# 1379_control.net
KiCad netlist of a schematic drawn in EAGLE
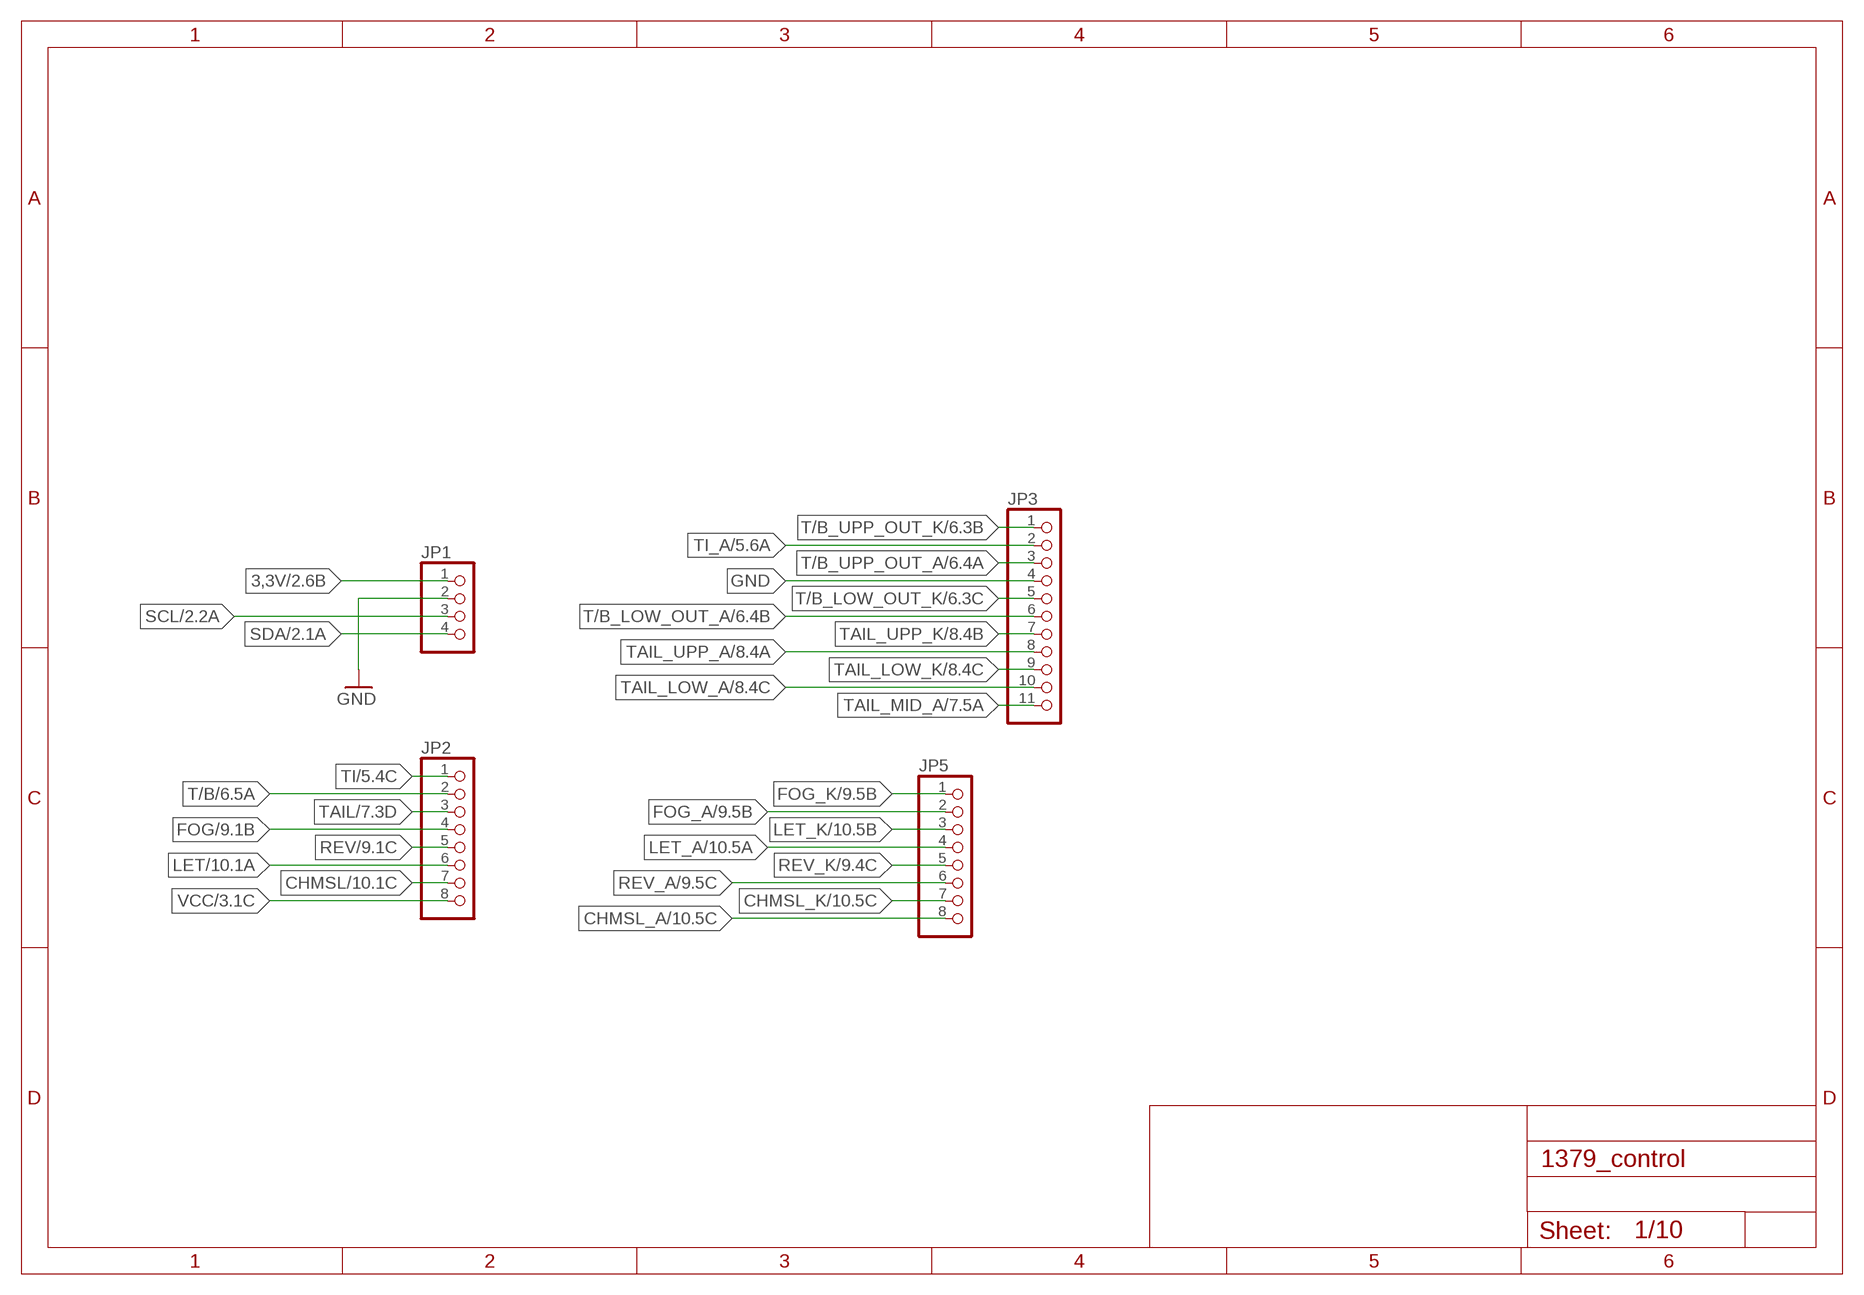
[diagram p0: schematic, sheet 1]
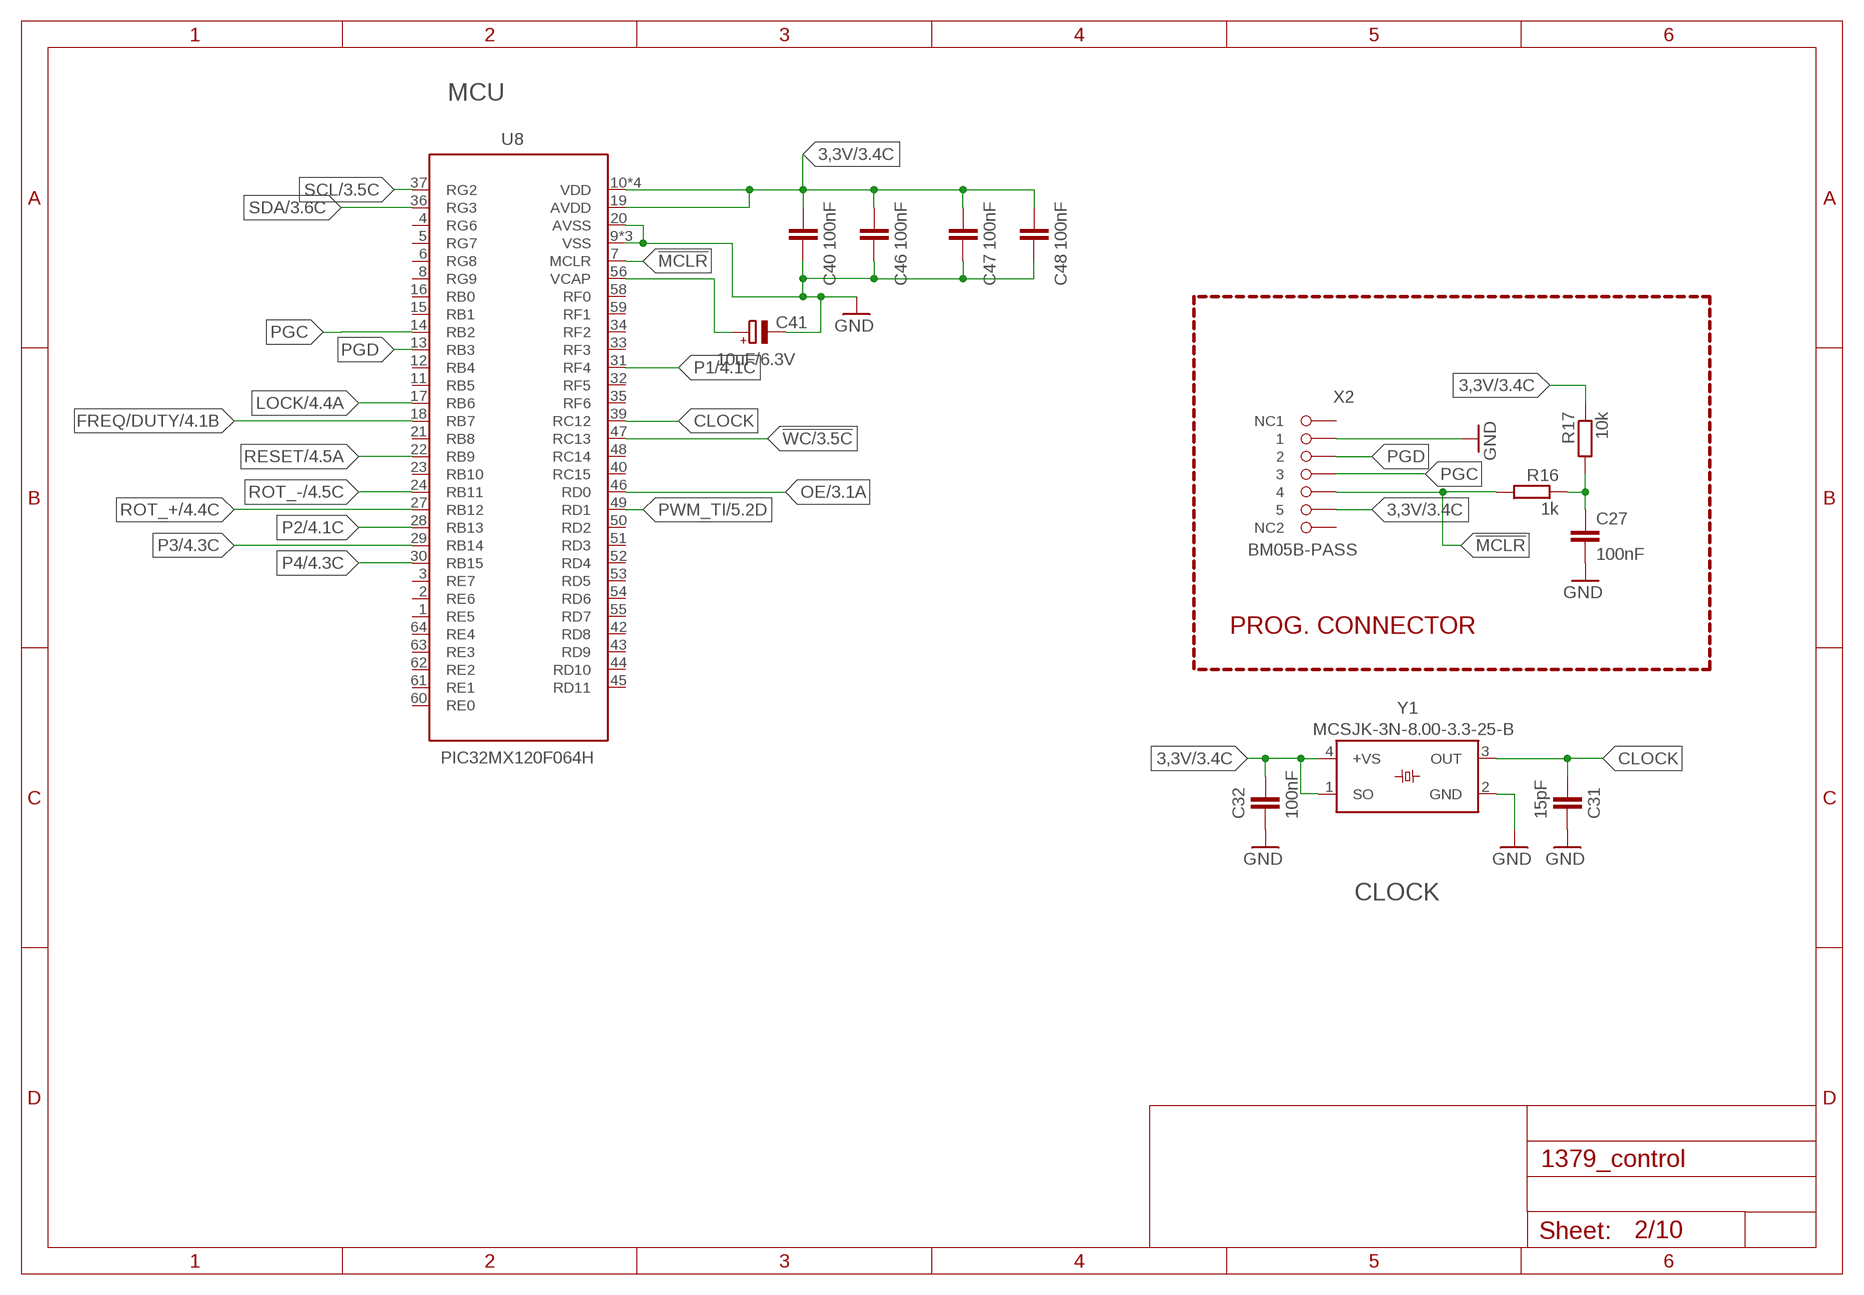
[diagram p1: schematic, sheet 2]
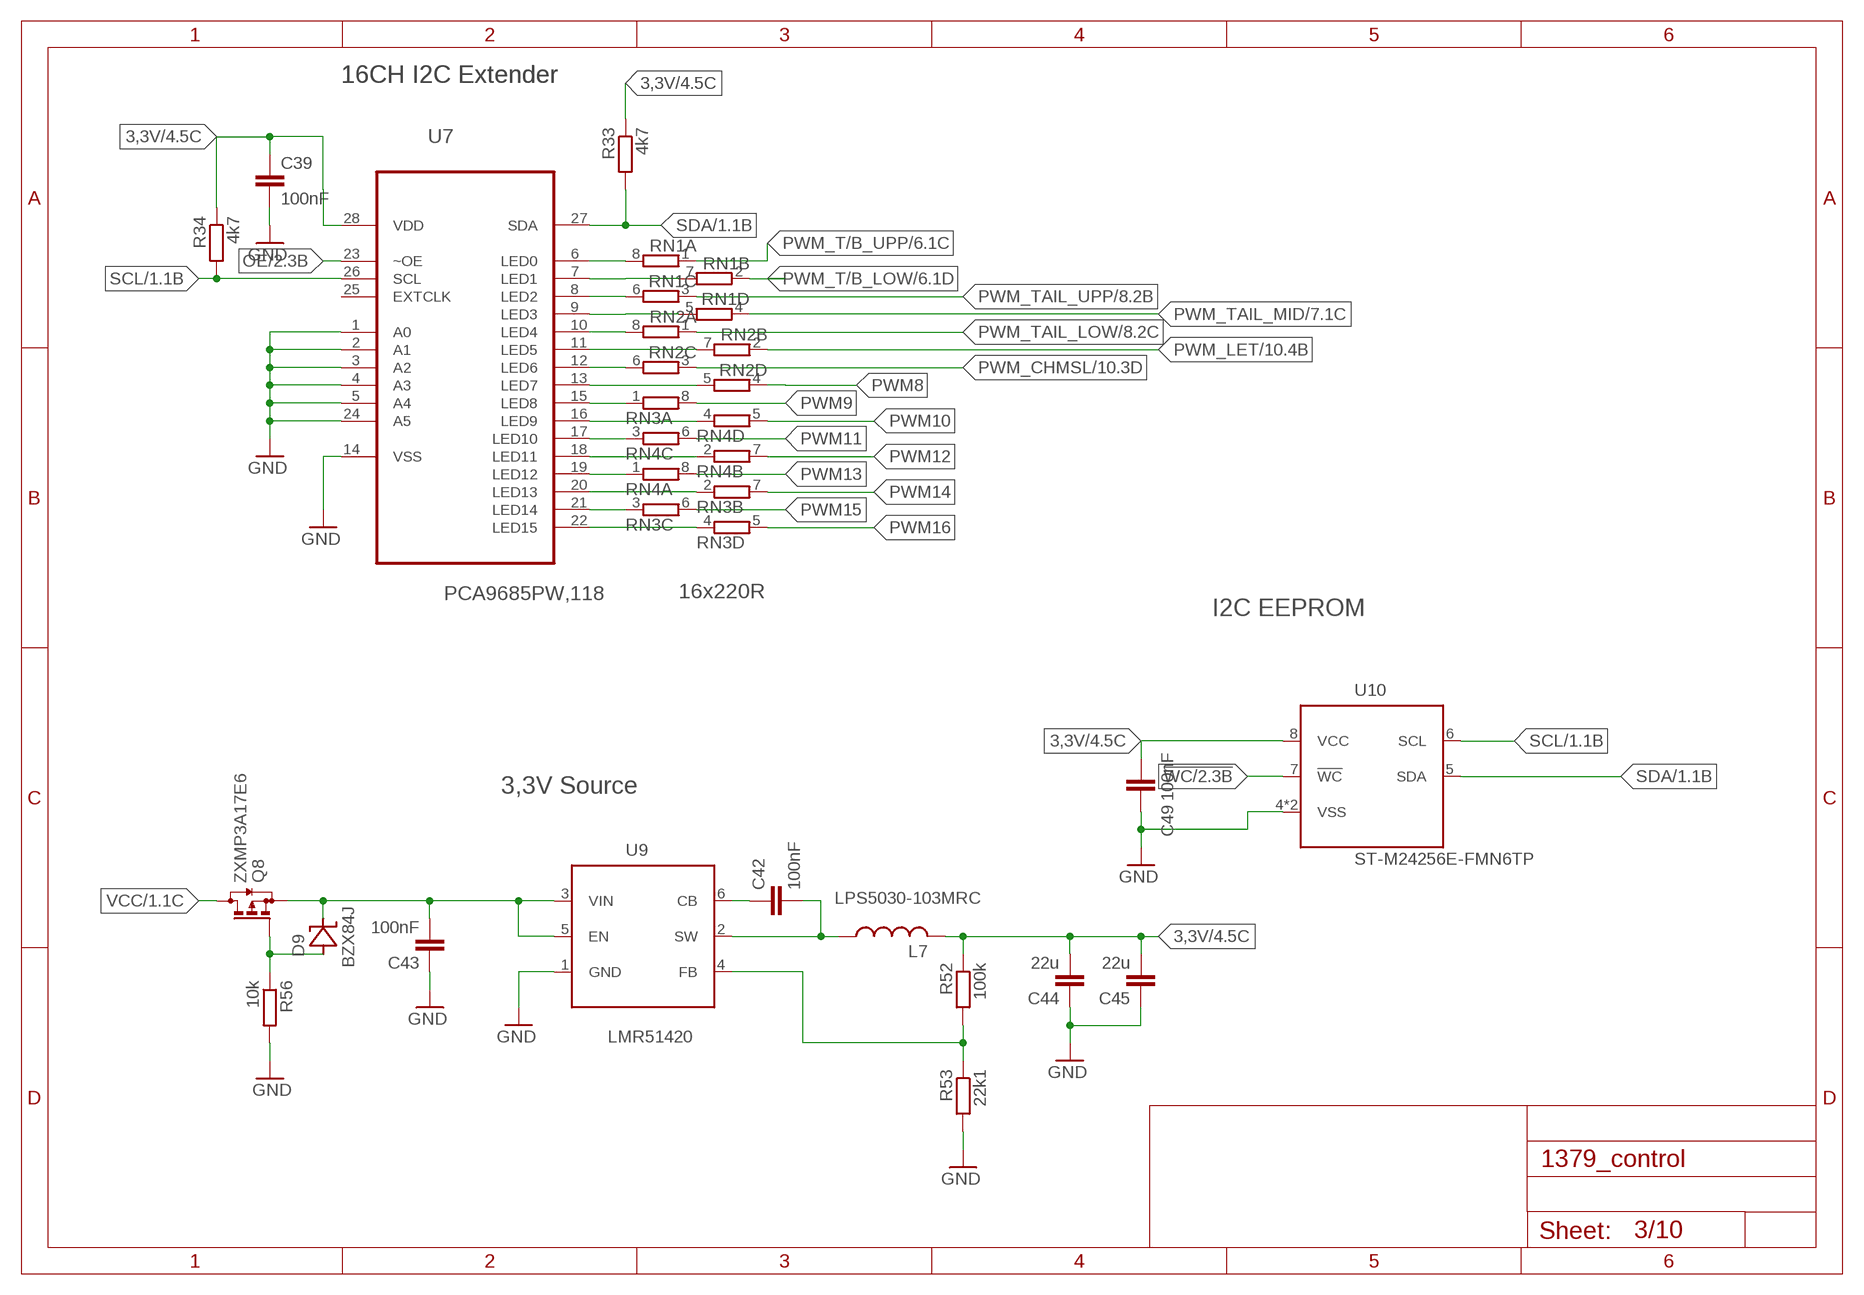
[diagram p2: schematic, sheet 3]
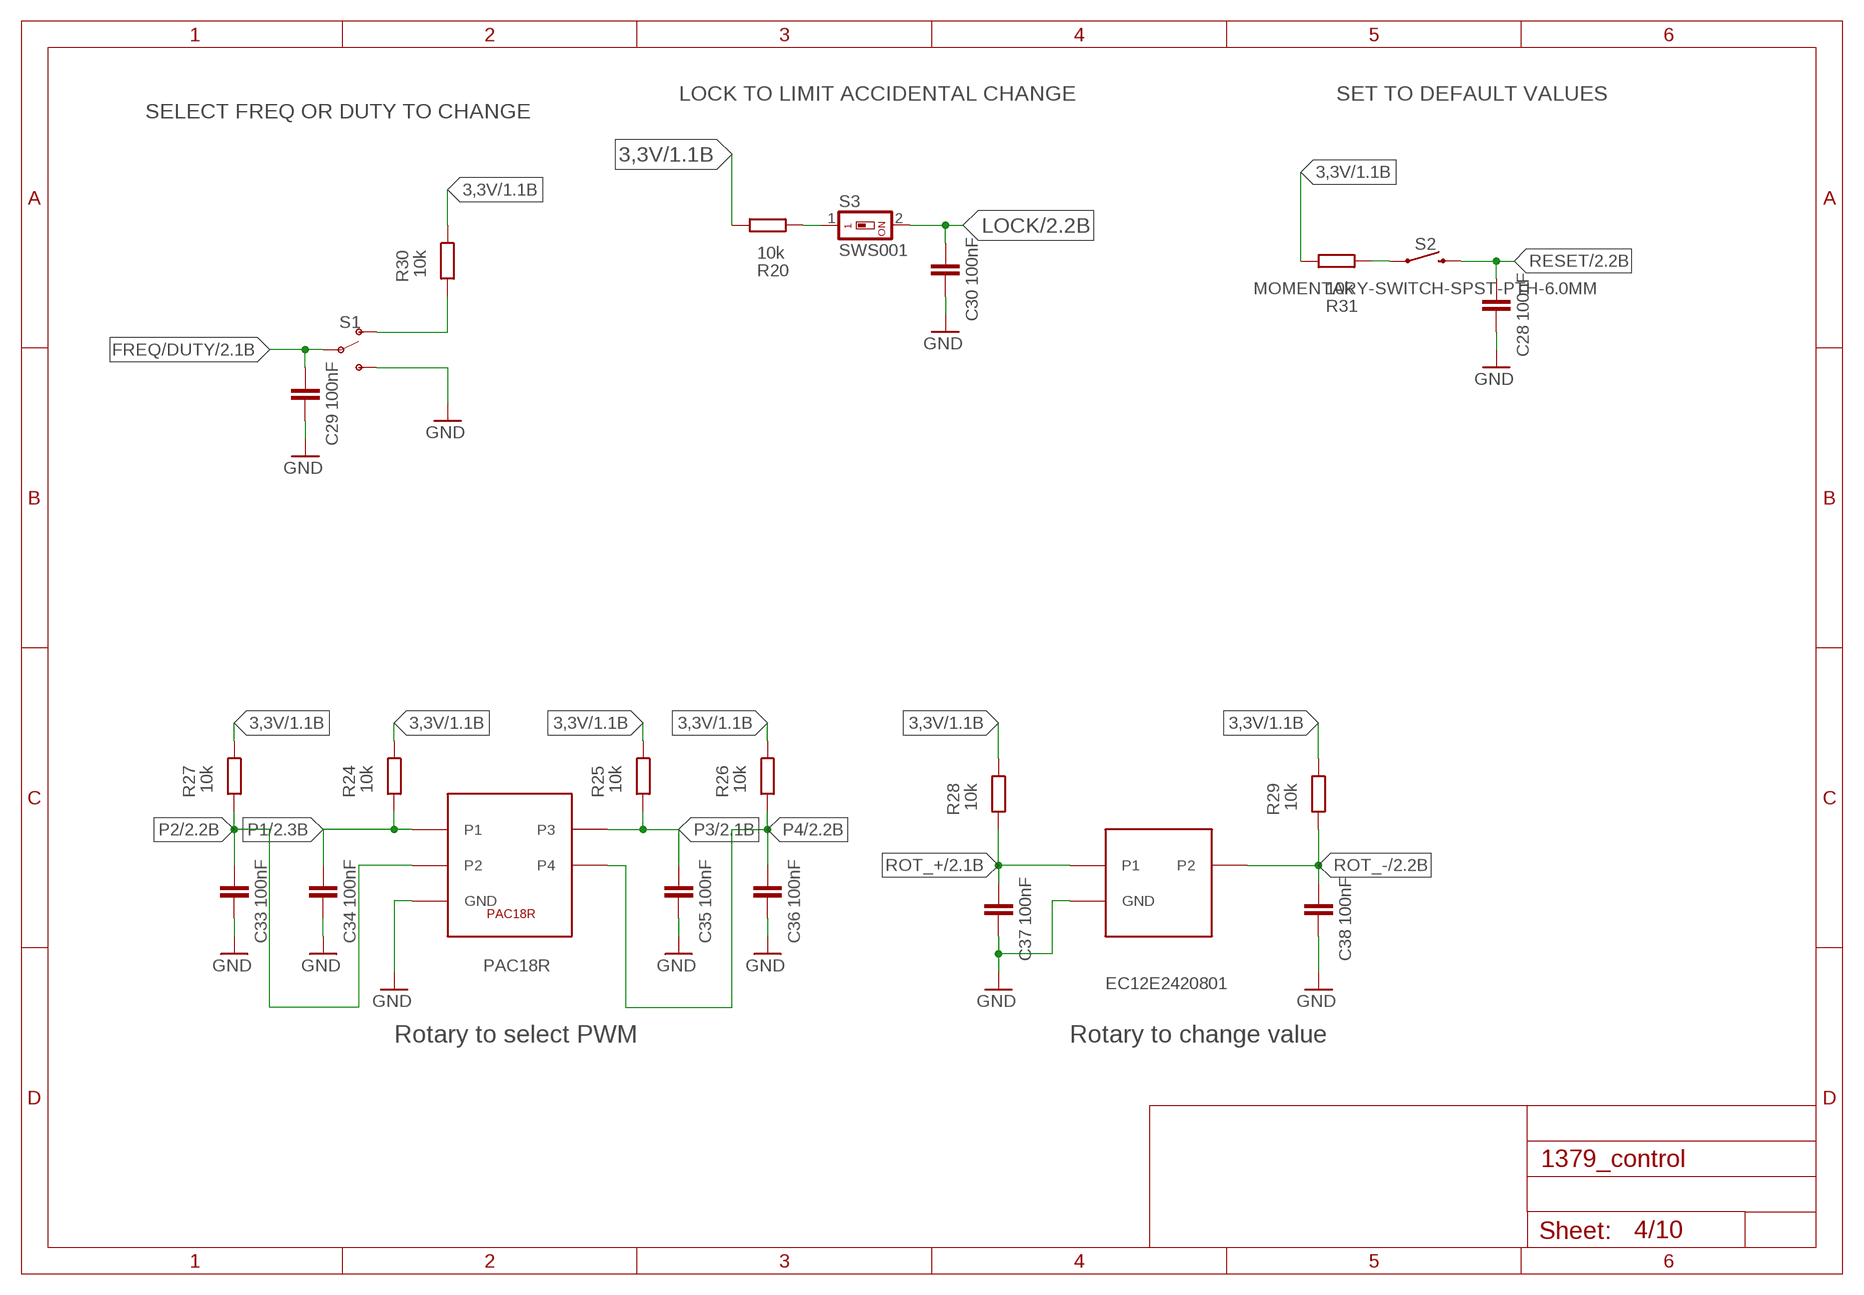
[diagram p3: schematic, sheet 4]
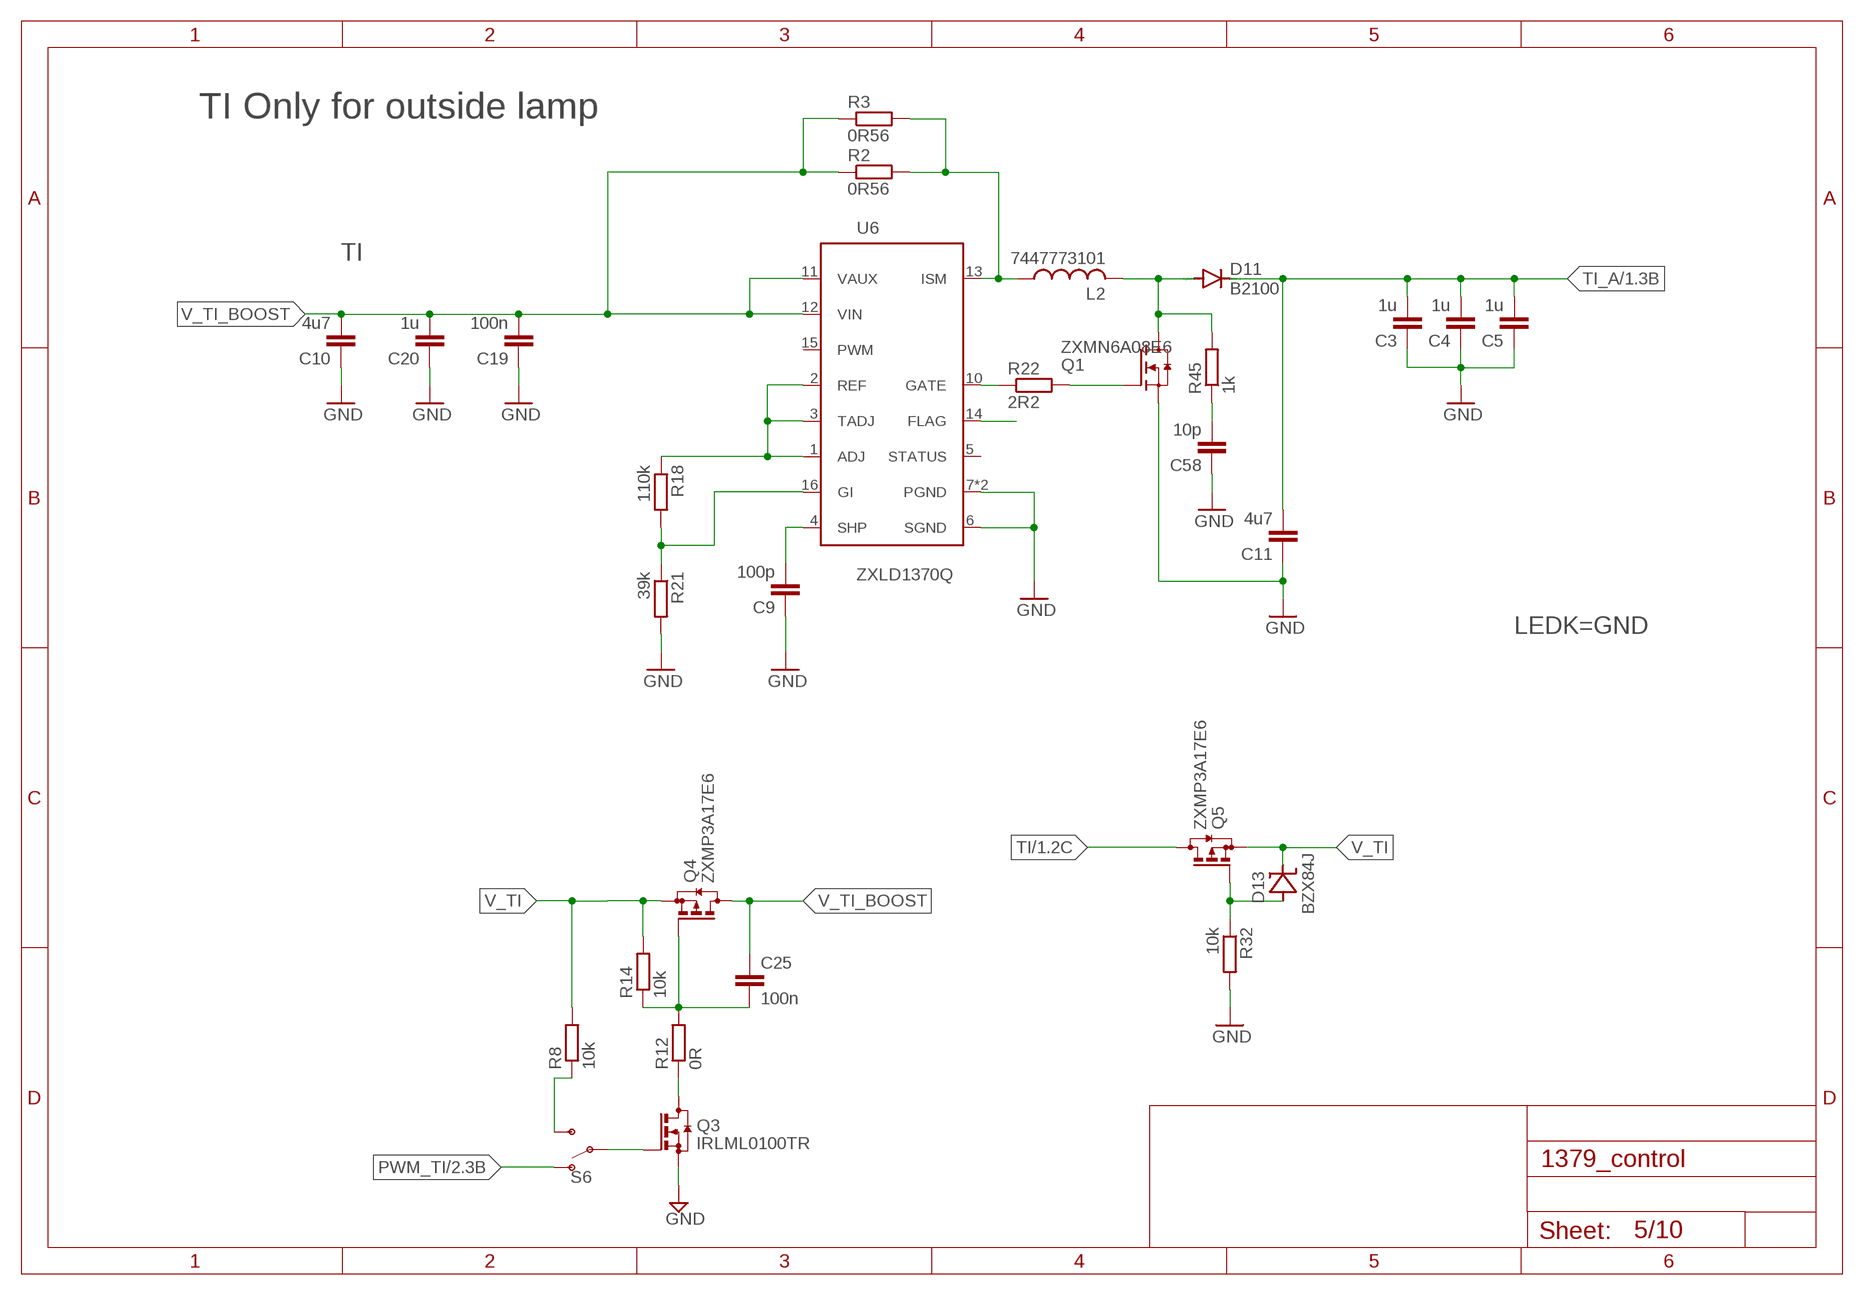
[diagram p4: schematic, sheet 5]
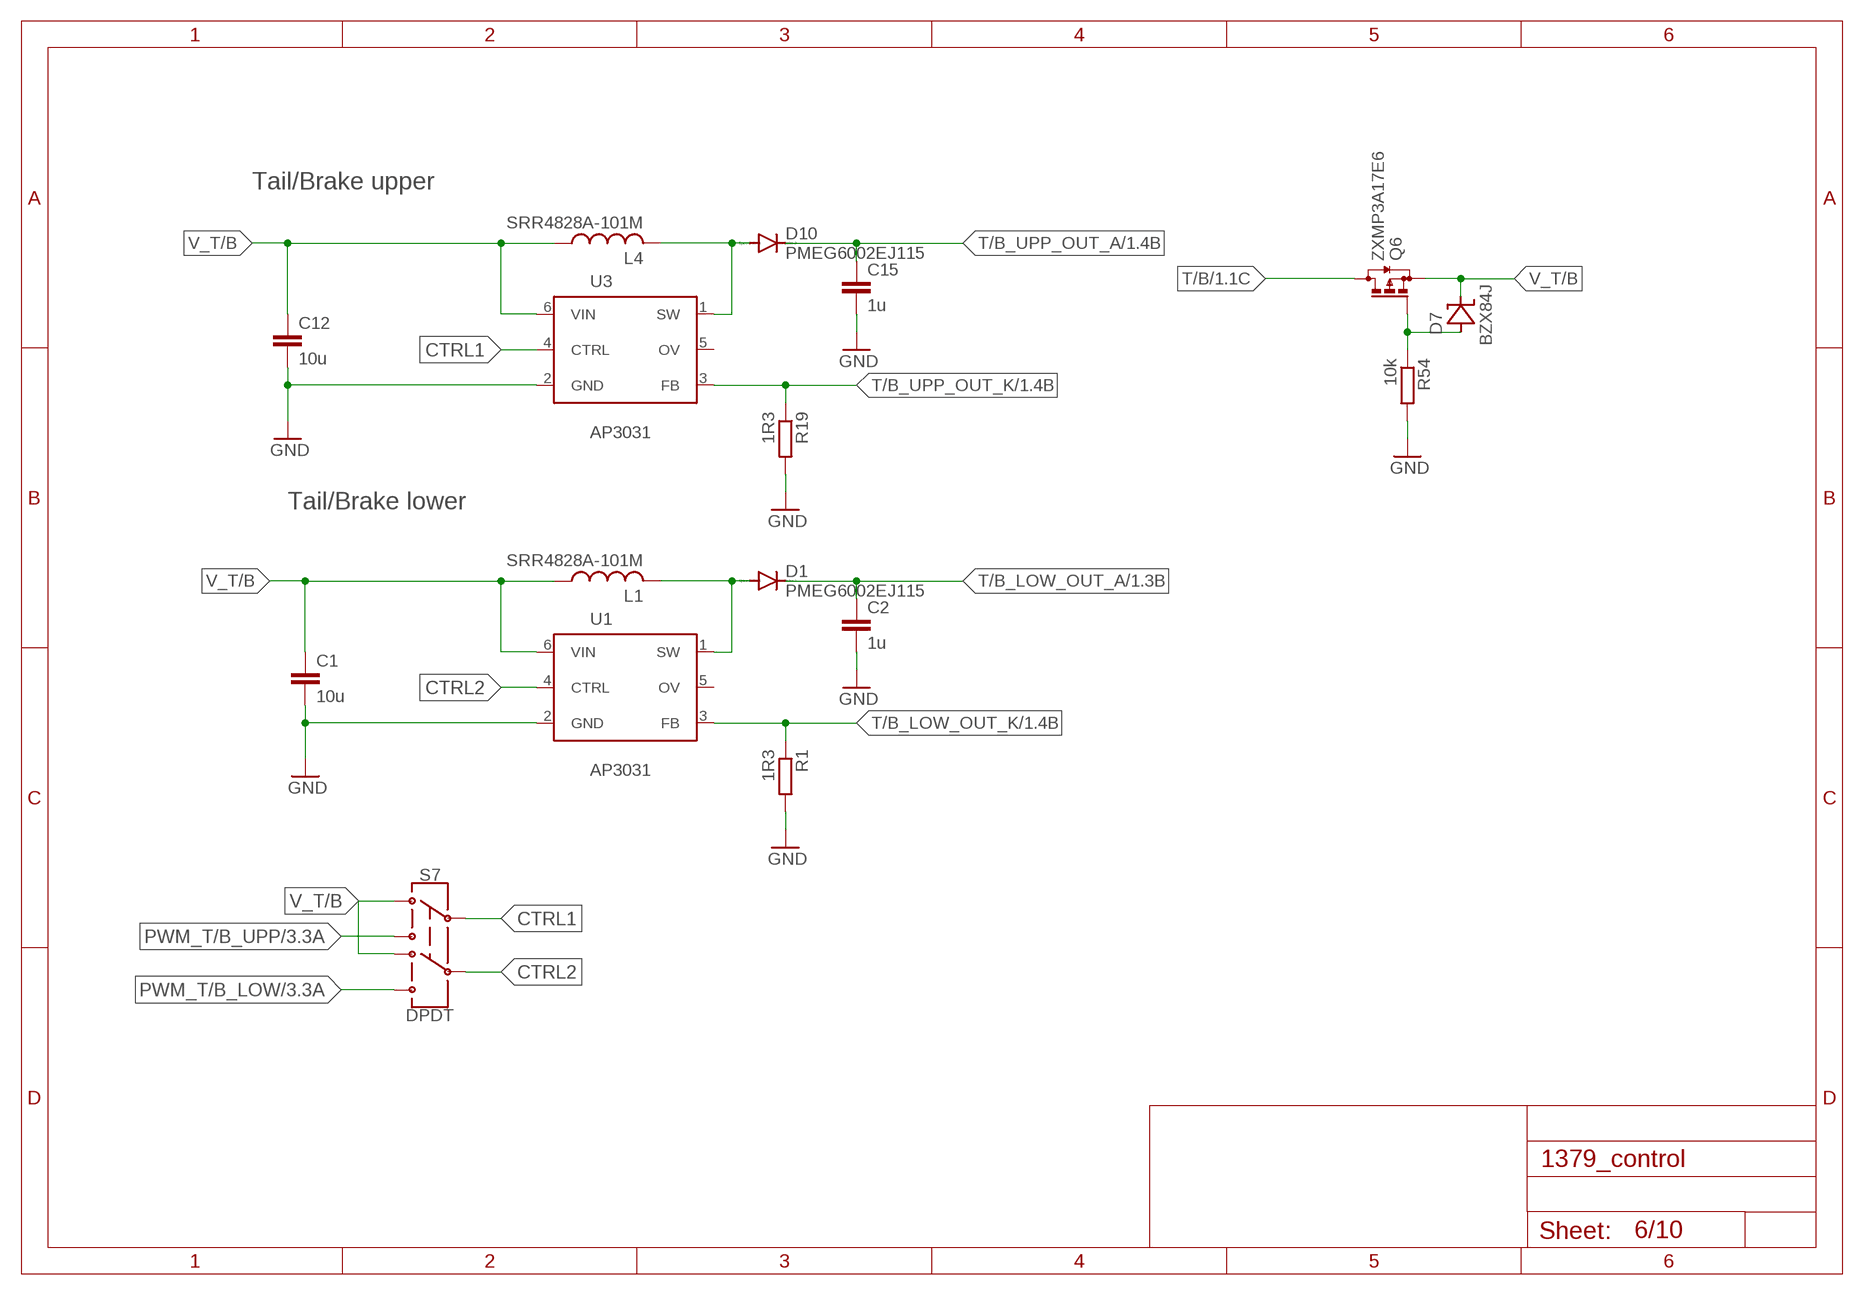
[diagram p5: schematic, sheet 6]
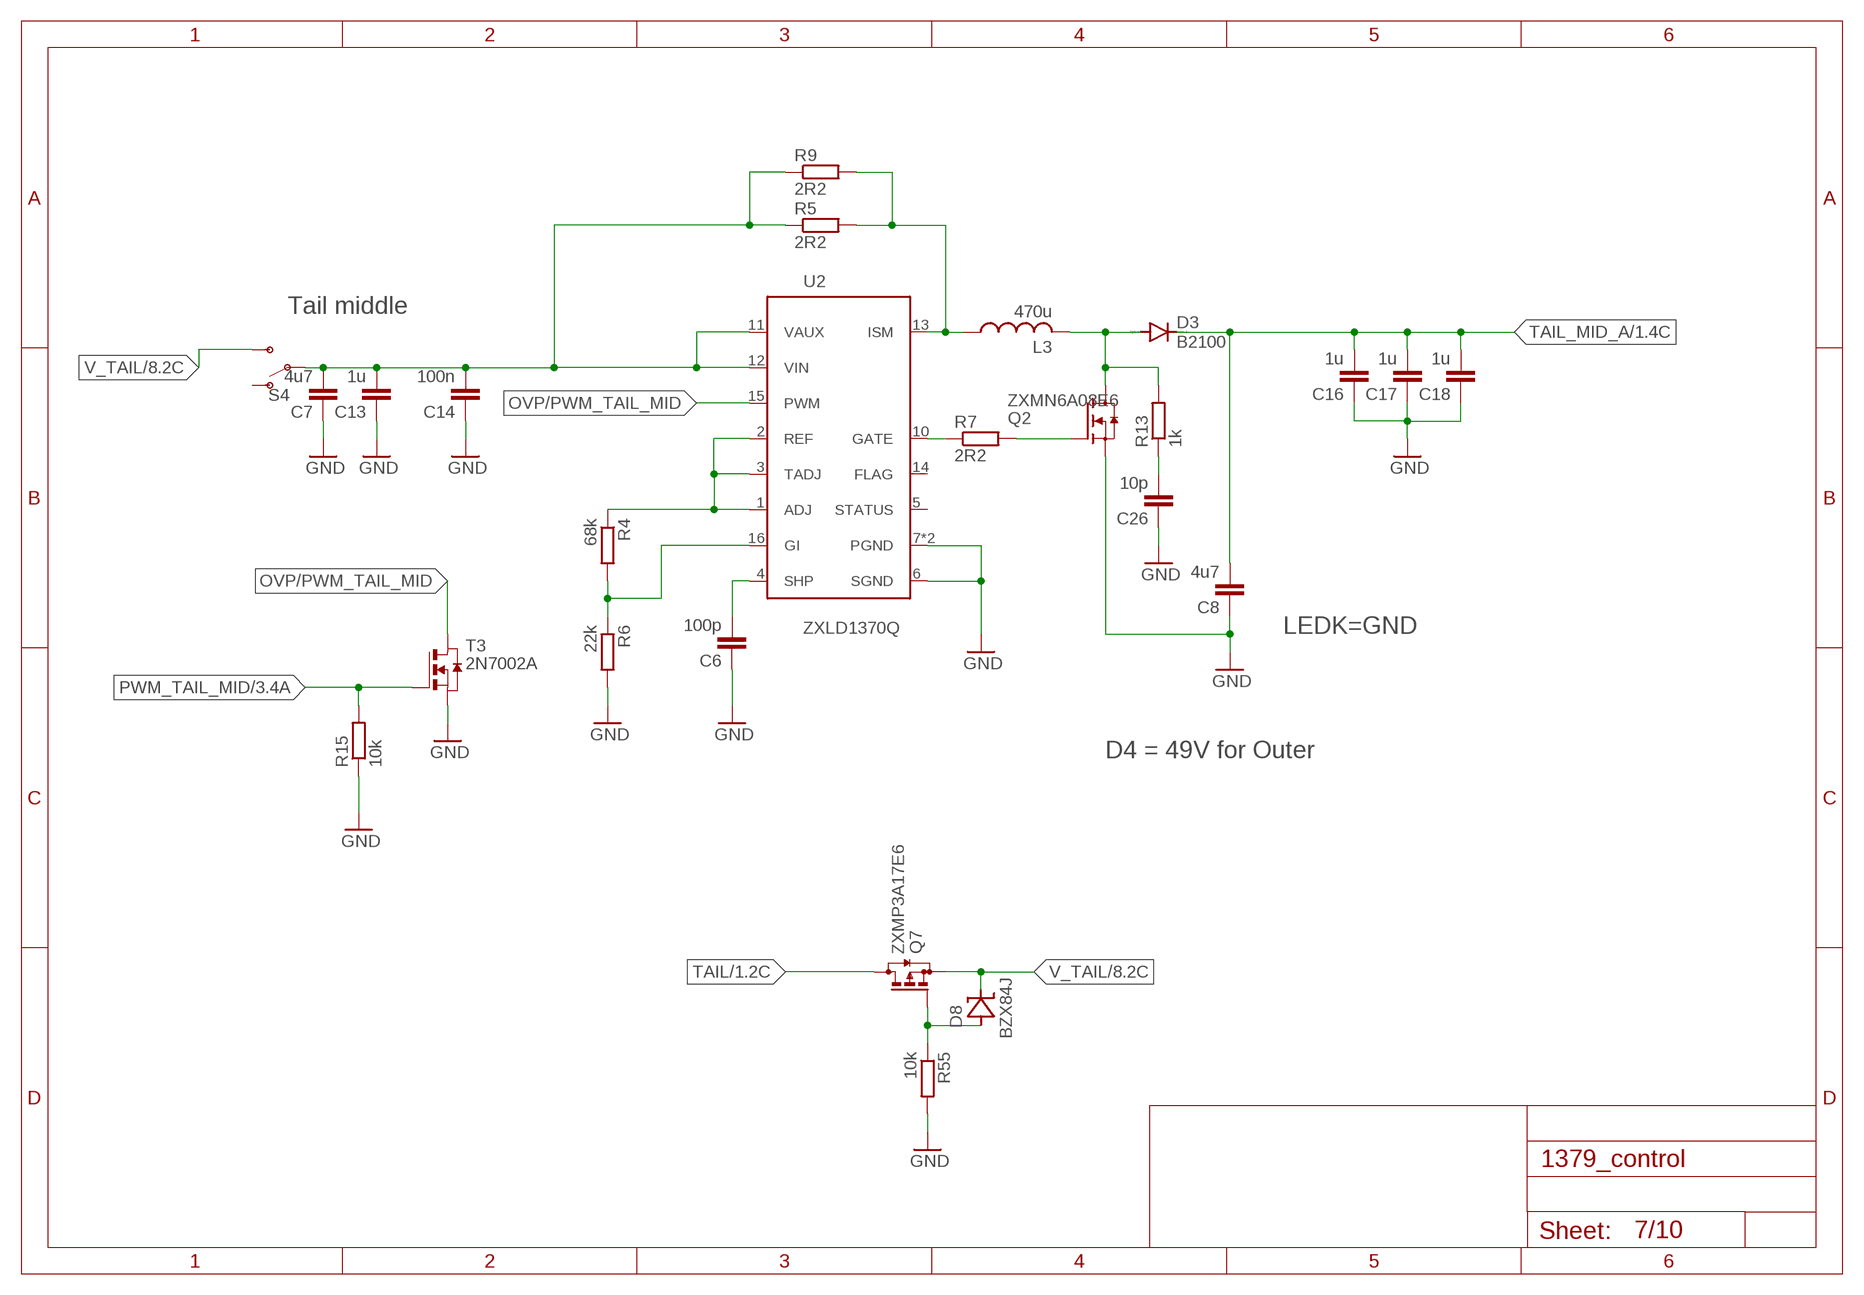
[diagram p6: schematic, sheet 7]
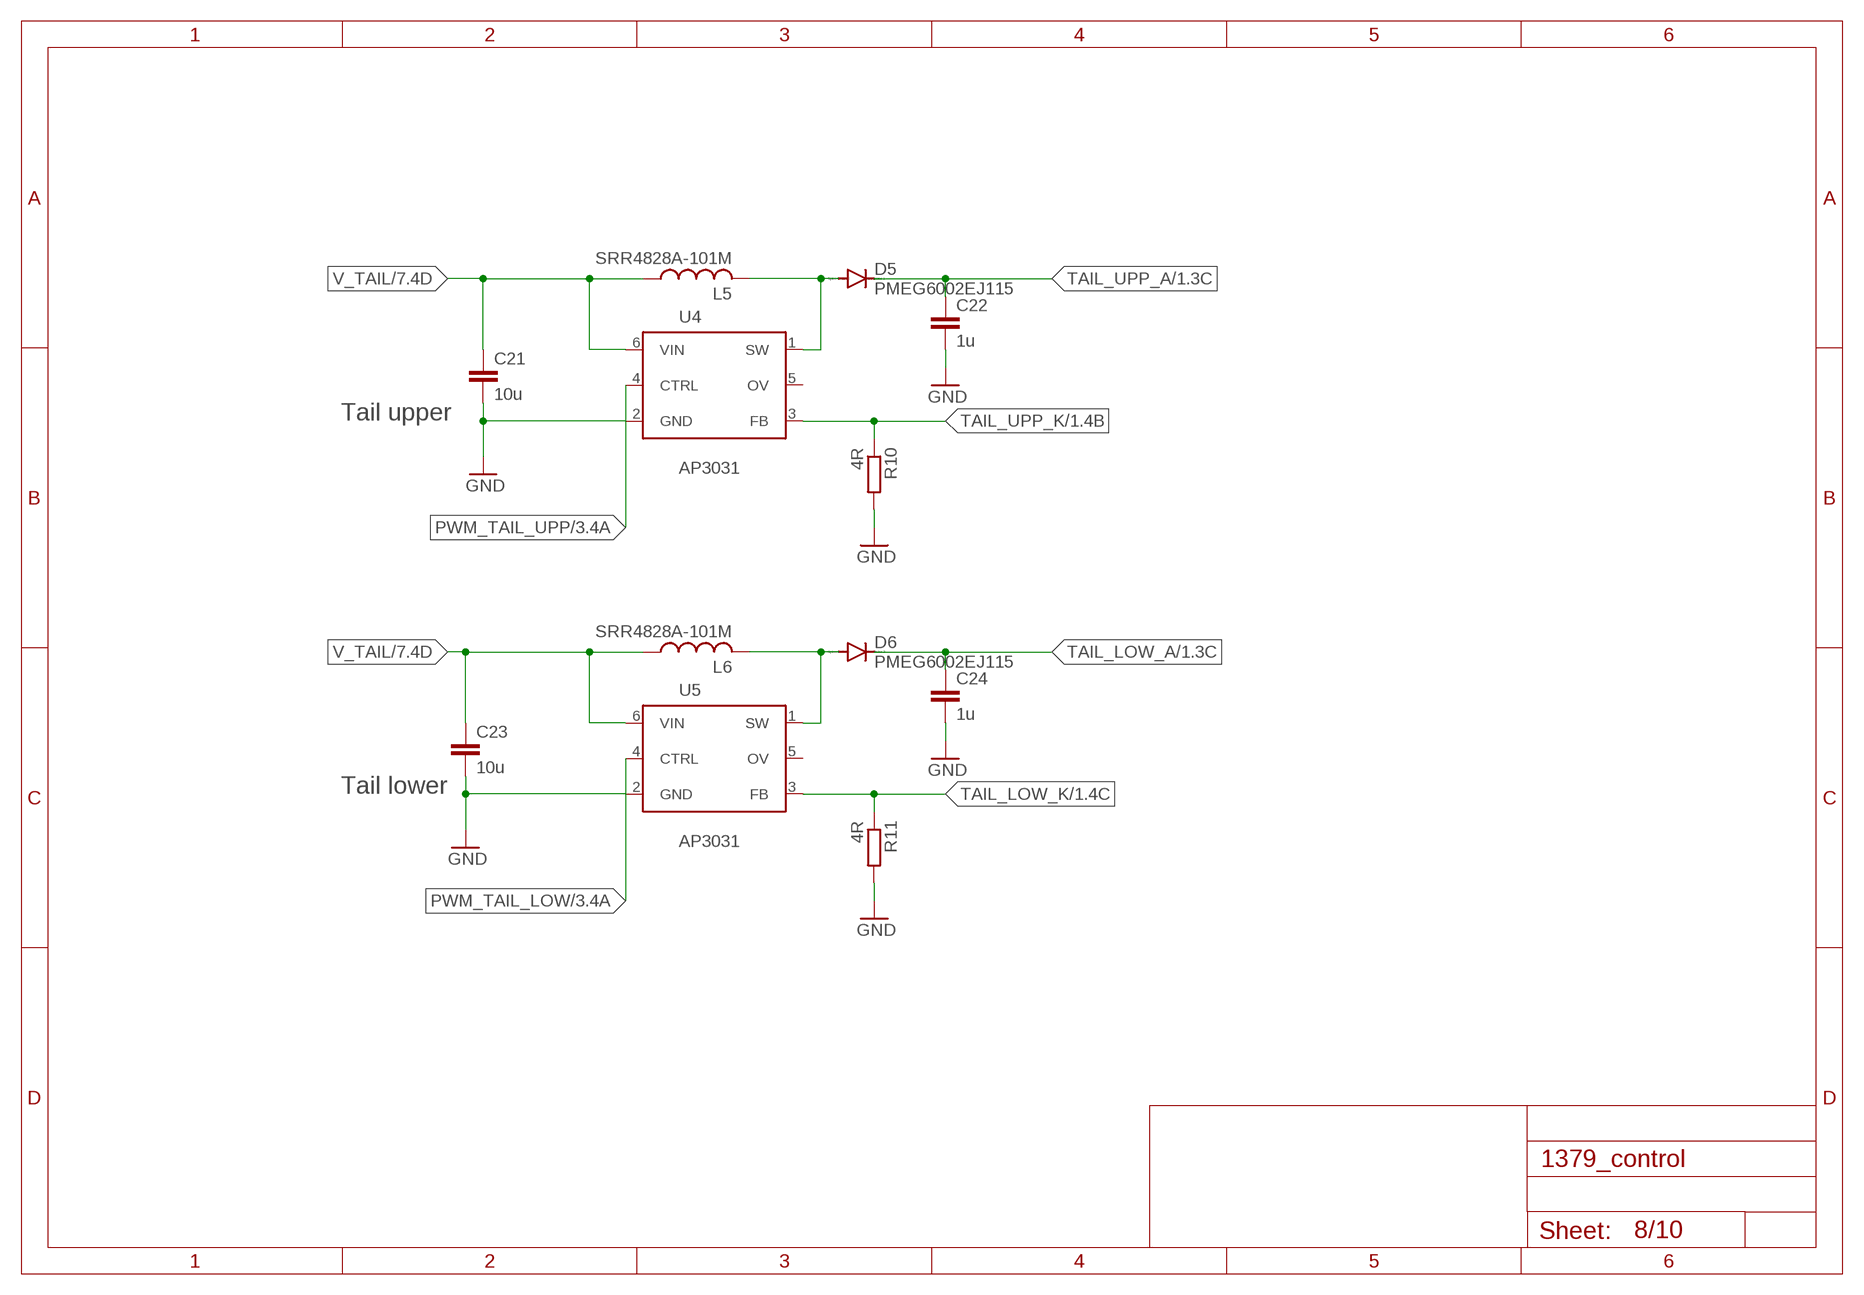
[diagram p7: schematic, sheet 8]
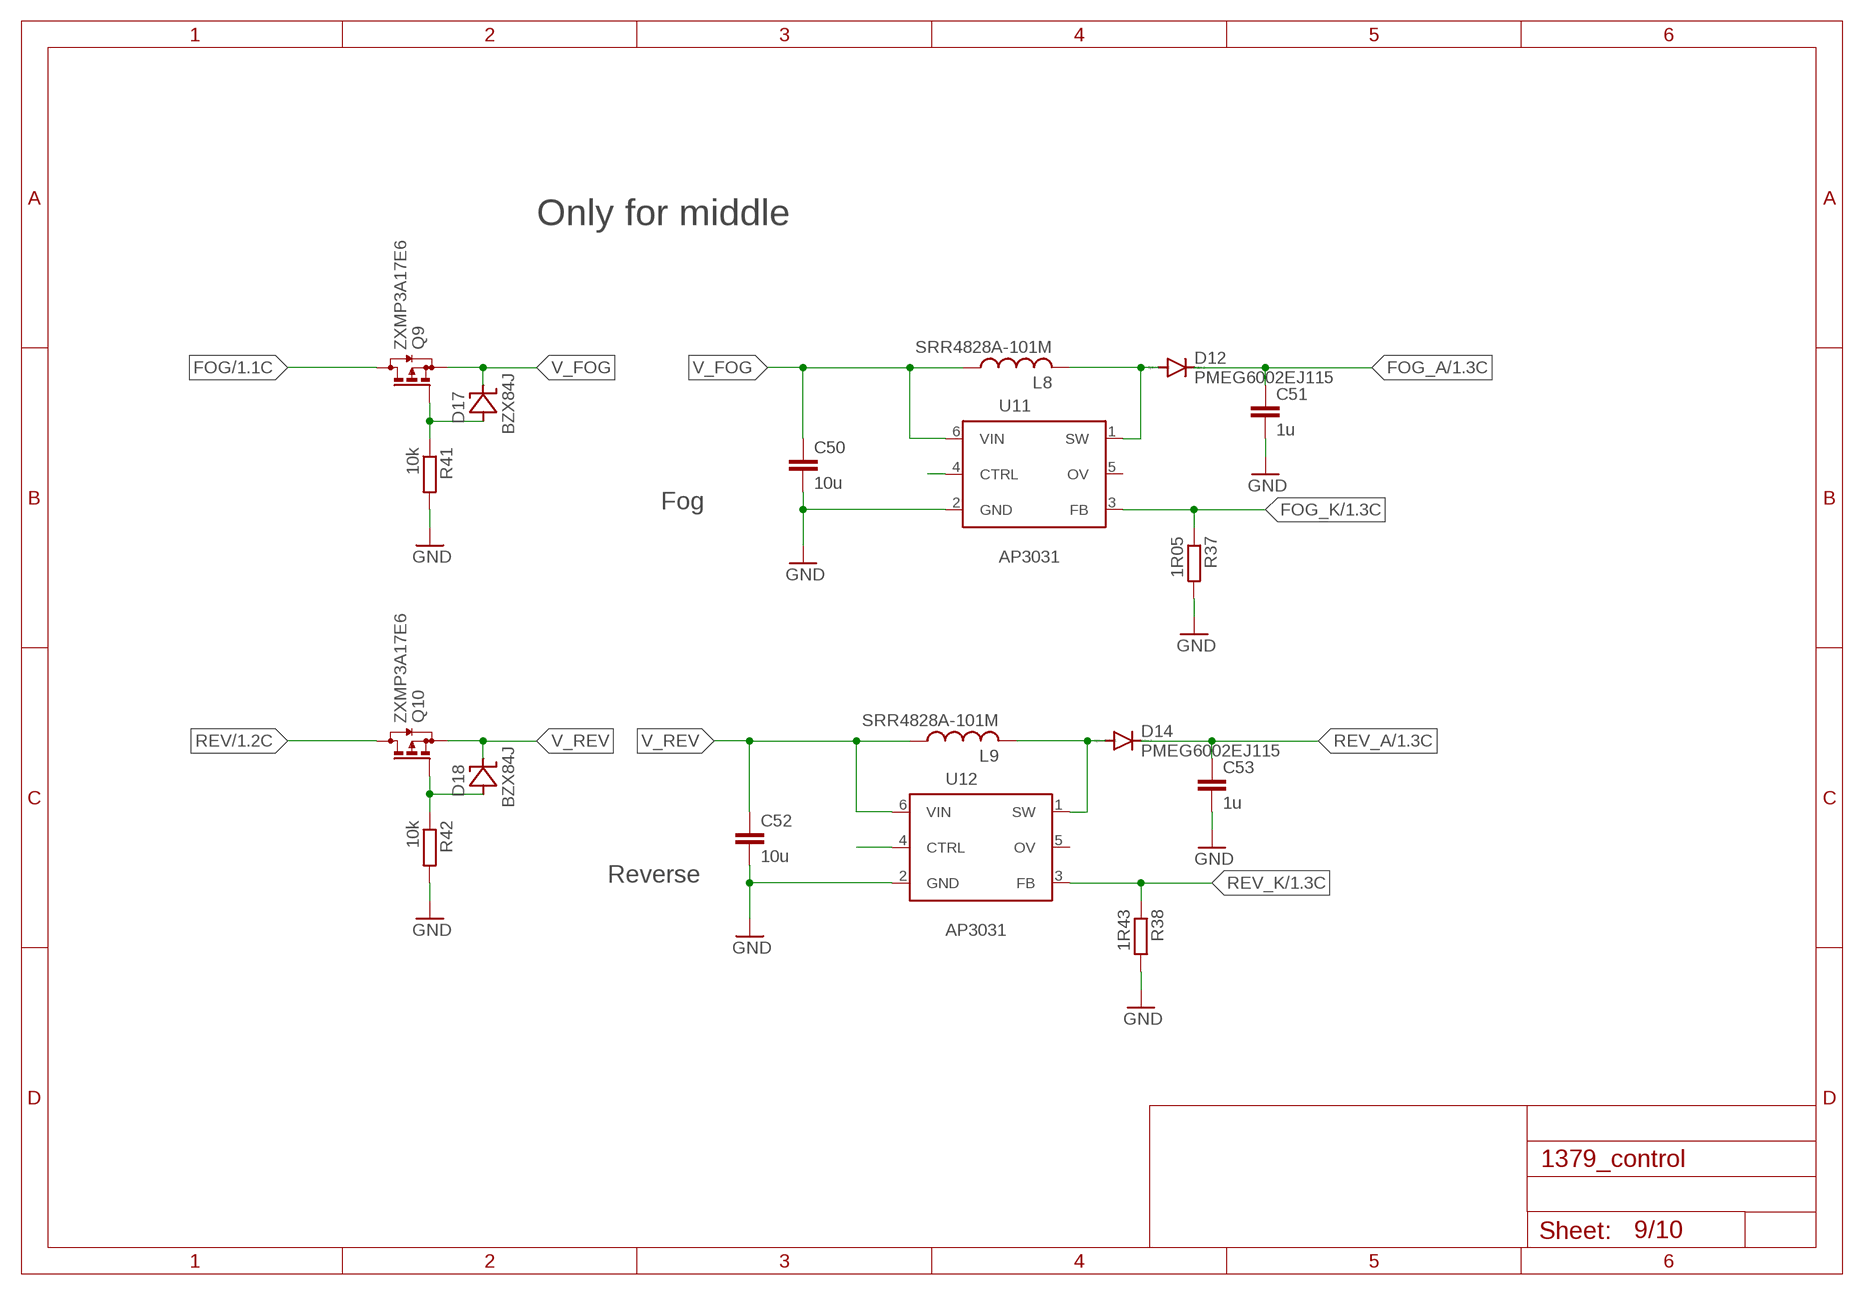
[diagram p8: schematic, sheet 9]
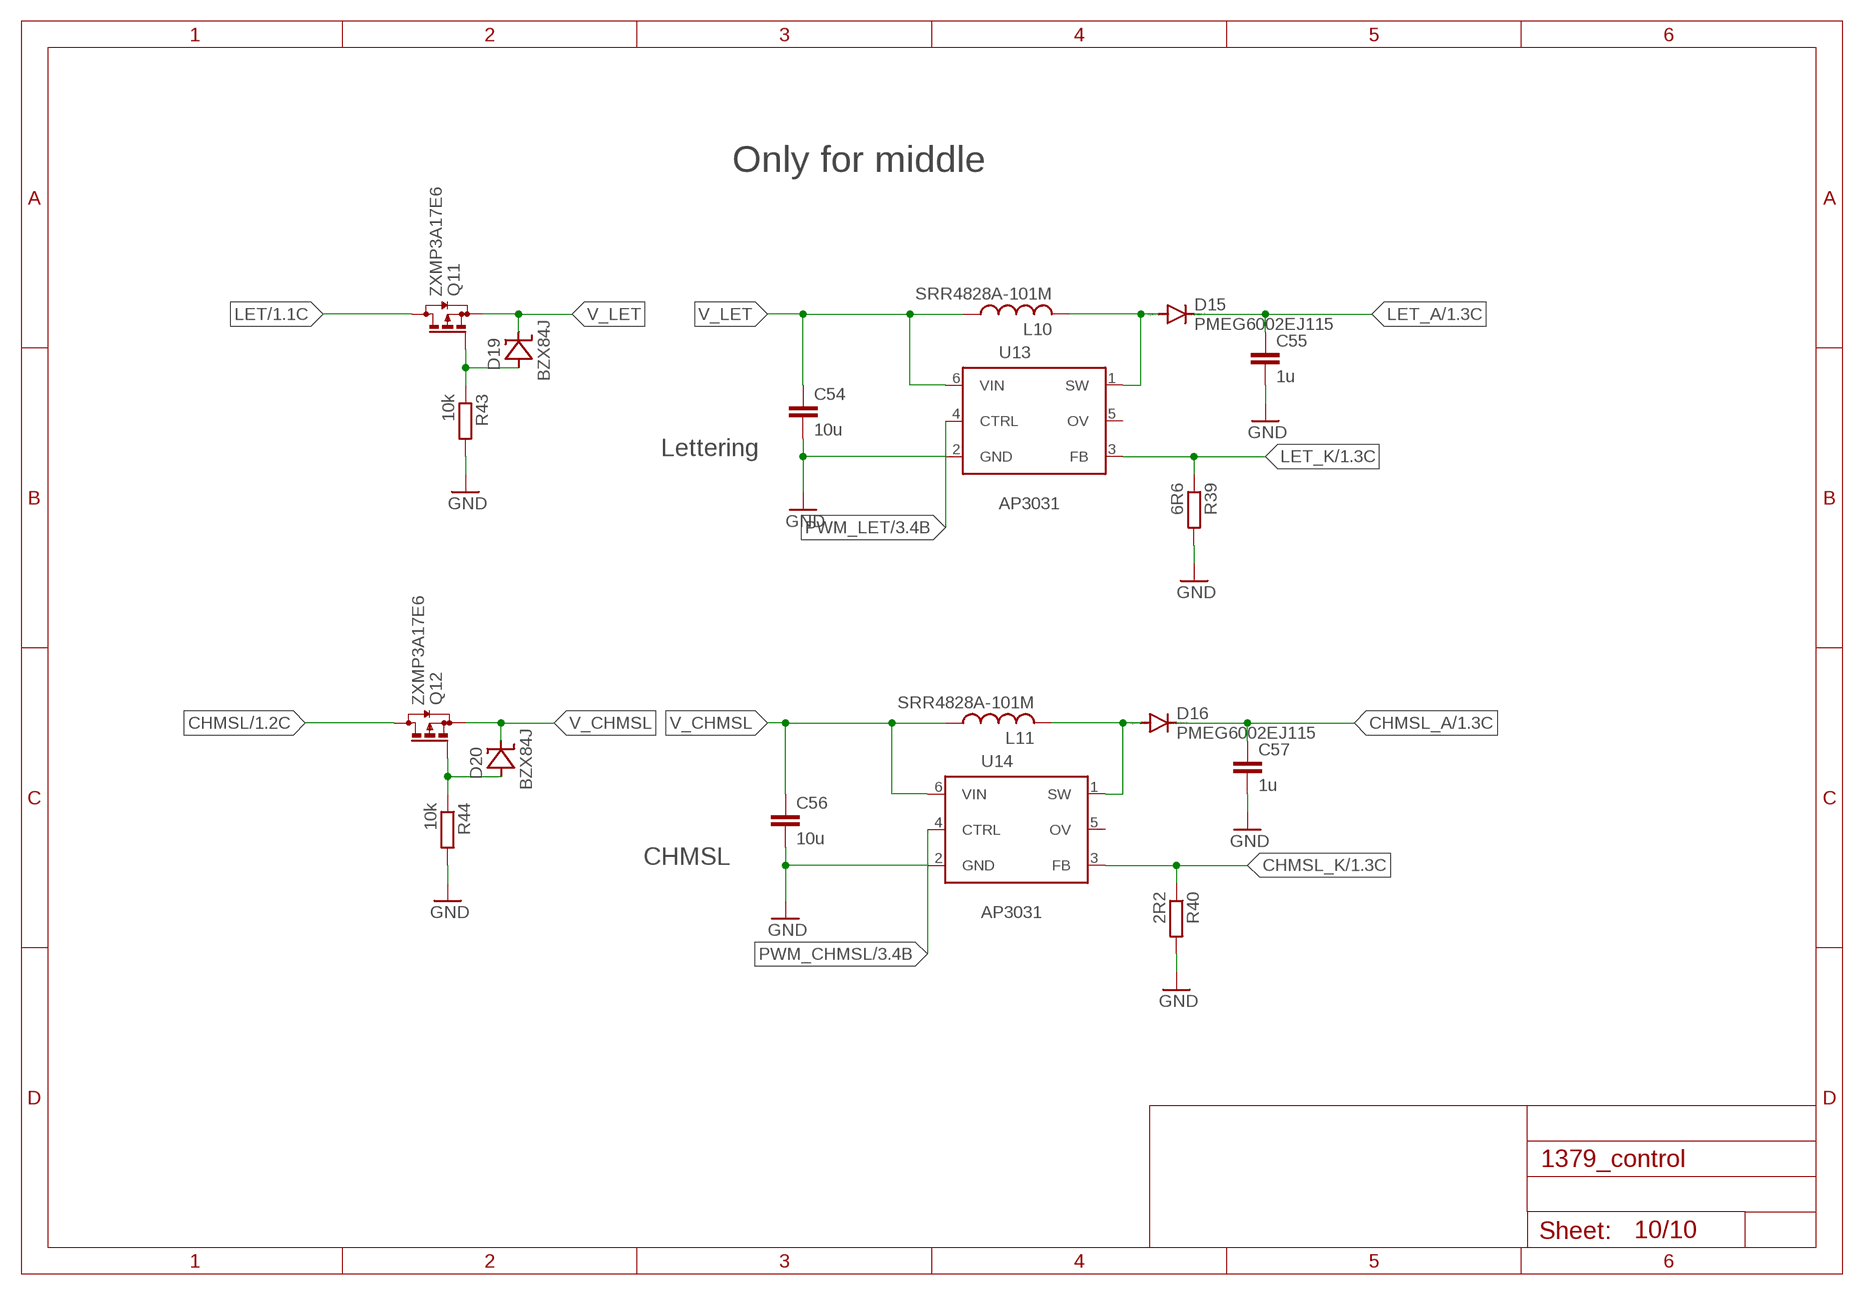
[diagram p9: schematic, sheet 10]

(export (version "E")
  (design (tool "Eeschema 10.0.6"))
  (components
    (comp (ref "C1")
      (value "10u")
      (footprint "eagle-import:C0805")
      (libsource (lib "eagle-import") (part "rcl_334_C-EUC0805"))
    )
    (comp (ref "C2")
      (value "1u")
      (footprint "eagle-import:C0805")
      (libsource (lib "eagle-import") (part "rcl_334_C-EUC0805"))
    )
    (comp (ref "C12")
      (value "10u")
      (footprint "eagle-import:C0805")
      (libsource (lib "eagle-import") (part "rcl_334_C-EUC0805"))
    )
    (comp (ref "C15")
      (value "1u")
      (footprint "eagle-import:C0805")
      (libsource (lib "eagle-import") (part "rcl_334_C-EUC0805"))
    )
    (comp (ref "D1")
      (value "PMEG6002EJ115")
      (footprint "eagle-import:SOD323-R")
      (libsource (lib "eagle-import") (part "DIODE-SOD323-R"))
    )
    (comp (ref "D7")
      (value "BZX84J")
      (footprint "eagle-import:SOD323")
      (libsource (lib "eagle-import") (part "BZX84J"))
    )
    (comp (ref "D10")
      (value "PMEG6002EJ115")
      (footprint "eagle-import:SOD323-R")
      (libsource (lib "eagle-import") (part "DIODE-SOD323-R"))
    )
    (comp (ref "L1")
      (value "SRR4828A-101M")
      (footprint "eagle-import:L_5X5")
      (libsource (lib "eagle-import") (part "POWER_INDUCTOR5X5"))
    )
    (comp (ref "L4")
      (value "SRR4828A-101M")
      (footprint "eagle-import:L_5X5")
      (libsource (lib "eagle-import") (part "POWER_INDUCTOR5X5"))
    )
    (comp (ref "Q6")
      (value "ZXMP3A17E6")
      (footprint "eagle-import:SOT23-6")
      (libsource (lib "eagle-import") (part "ZXMP3A17E6"))
    )
    (comp (ref "R1")
      (value "1R3")
      (footprint "eagle-import:R0805")
      (libsource (lib "eagle-import") (part "rcl_334_R-EU_R0805"))
    )
    (comp (ref "R19")
      (value "1R3")
      (footprint "eagle-import:R0805")
      (libsource (lib "eagle-import") (part "rcl_334_R-EU_R0805"))
    )
    (comp (ref "R54")
      (value "10k")
      (footprint "eagle-import:R0603")
      (libsource (lib "eagle-import") (part "rcl_334_R-EU_R0603"))
    )
    (comp (ref "S7")
      (value "DPDT")
      (footprint "eagle-import:SWITCH_DPDT_PTH_GPI-152-3013")
      (libsource (lib "eagle-import") (part "DPDT"))
    )
    (comp (ref "U1")
      (value "AP3031")
      (footprint "eagle-import:SOT23-6")
      (libsource (lib "eagle-import") (part "AP3031"))
    )
    (comp (ref "U3")
      (value "AP3031")
      (footprint "eagle-import:SOT23-6")
      (libsource (lib "eagle-import") (part "AP3031"))
    )
    (comp (ref "C54")
      (value "10u")
      (footprint "eagle-import:C0805")
      (libsource (lib "eagle-import") (part "rcl_334_C-EUC0805"))
    )
    (comp (ref "C55")
      (value "1u")
      (footprint "eagle-import:C0805")
      (libsource (lib "eagle-import") (part "rcl_334_C-EUC0805"))
    )
    (comp (ref "C56")
      (value "10u")
      (footprint "eagle-import:C0805")
      (libsource (lib "eagle-import") (part "rcl_334_C-EUC0805"))
    )
    (comp (ref "C57")
      (value "1u")
      (footprint "eagle-import:C0805")
      (libsource (lib "eagle-import") (part "rcl_334_C-EUC0805"))
    )
    (comp (ref "D15")
      (value "PMEG6002EJ115")
      (footprint "eagle-import:SOD323-R")
      (libsource (lib "eagle-import") (part "DIODE-SOD323-R"))
    )
    (comp (ref "D16")
      (value "PMEG6002EJ115")
      (footprint "eagle-import:SOD323-R")
      (libsource (lib "eagle-import") (part "DIODE-SOD323-R"))
    )
    (comp (ref "D19")
      (value "BZX84J")
      (footprint "eagle-import:SOD323")
      (libsource (lib "eagle-import") (part "BZX84J"))
    )
    (comp (ref "D20")
      (value "BZX84J")
      (footprint "eagle-import:SOD323")
      (libsource (lib "eagle-import") (part "BZX84J"))
    )
    (comp (ref "L10")
      (value "SRR4828A-101M")
      (footprint "eagle-import:L_5X5")
      (libsource (lib "eagle-import") (part "POWER_INDUCTOR5X5"))
    )
    (comp (ref "L11")
      (value "SRR4828A-101M")
      (footprint "eagle-import:L_5X5")
      (libsource (lib "eagle-import") (part "POWER_INDUCTOR5X5"))
    )
    (comp (ref "Q11")
      (value "ZXMP3A17E6")
      (footprint "eagle-import:SOT23-6")
      (libsource (lib "eagle-import") (part "ZXMP3A17E6"))
    )
    (comp (ref "Q12")
      (value "ZXMP3A17E6")
      (footprint "eagle-import:SOT23-6")
      (libsource (lib "eagle-import") (part "ZXMP3A17E6"))
    )
    (comp (ref "R39")
      (value "6R6")
      (footprint "eagle-import:R0805")
      (libsource (lib "eagle-import") (part "rcl_334_R-EU_R0805"))
    )
    (comp (ref "R40")
      (value "2R2")
      (footprint "eagle-import:R0805")
      (libsource (lib "eagle-import") (part "rcl_334_R-EU_R0805"))
    )
    (comp (ref "R43")
      (value "10k")
      (footprint "eagle-import:R0603")
      (libsource (lib "eagle-import") (part "rcl_334_R-EU_R0603"))
    )
    (comp (ref "R44")
      (value "10k")
      (footprint "eagle-import:R0603")
      (libsource (lib "eagle-import") (part "rcl_334_R-EU_R0603"))
    )
    (comp (ref "U13")
      (value "AP3031")
      (footprint "eagle-import:SOT23-6")
      (libsource (lib "eagle-import") (part "AP3031"))
    )
    (comp (ref "U14")
      (value "AP3031")
      (footprint "eagle-import:SOT23-6")
      (libsource (lib "eagle-import") (part "AP3031"))
    )
    (comp (ref "C39")
      (value "100nF")
      (footprint "eagle-import:C0603")
      (libsource (lib "eagle-import") (part "C-EUC0603"))
    )
    (comp (ref "C42")
      (value "100nF")
      (footprint "eagle-import:C0603")
      (libsource (lib "eagle-import") (part "C-EUC0603"))
    )
    (comp (ref "C43")
      (value "100nF")
      (footprint "eagle-import:C0603")
      (libsource (lib "eagle-import") (part "C-EUC0603"))
    )
    (comp (ref "C44")
      (value "22u")
      (footprint "eagle-import:C0603")
      (libsource (lib "eagle-import") (part "C-EUC0603"))
    )
    (comp (ref "C45")
      (value "22u")
      (footprint "eagle-import:C0603")
      (libsource (lib "eagle-import") (part "C-EUC0603"))
    )
    (comp (ref "C49")
      (value "100nF")
      (footprint "eagle-import:C0603")
      (libsource (lib "eagle-import") (part "rcl_334_C-EUC0603"))
    )
    (comp (ref "D9")
      (value "BZX84J")
      (footprint "eagle-import:SOD323")
      (libsource (lib "eagle-import") (part "BZX84J"))
    )
    (comp (ref "L7")
      (value "LPS5030-103MRC")
      (footprint "eagle-import:L_5X5")
      (libsource (lib "eagle-import") (part "POWER_INDUCTOR5X5"))
    )
    (comp (ref "Q8")
      (value "ZXMP3A17E6")
      (footprint "eagle-import:SOT23-6")
      (libsource (lib "eagle-import") (part "ZXMP3A17E6"))
    )
    (comp (ref "R33")
      (value "4k7")
      (footprint "eagle-import:R0603")
      (libsource (lib "eagle-import") (part "R-EU_R0603"))
    )
    (comp (ref "R34")
      (value "4k7")
      (footprint "eagle-import:R0603")
      (libsource (lib "eagle-import") (part "R-EU_R0603"))
    )
    (comp (ref "R52")
      (value "100k")
      (footprint "eagle-import:R0603")
      (libsource (lib "eagle-import") (part "R-EU_R0603"))
    )
    (comp (ref "R53")
      (value "22k1")
      (footprint "eagle-import:R0603")
      (libsource (lib "eagle-import") (part "R-EU_R0603"))
    )
    (comp (ref "R56")
      (value "10k")
      (footprint "eagle-import:R0603")
      (libsource (lib "eagle-import") (part "rcl_334_R-EU_R0603"))
    )
    (comp (ref "RN1")
      (value "4R-NEXBS8V")
      (footprint "eagle-import:EXBS8V")
      (libsource (lib "eagle-import") (part "4R-NEXBS8V"))
    )
    (comp (ref "RN2")
      (value "4R-NEXBS8V")
      (footprint "eagle-import:EXBS8V")
      (libsource (lib "eagle-import") (part "4R-NEXBS8V"))
    )
    (comp (ref "RN3")
      (value "4R-NEXBS8V")
      (footprint "eagle-import:EXBS8V")
      (libsource (lib "eagle-import") (part "4R-NEXBS8V"))
    )
    (comp (ref "RN4")
      (value "4R-NEXBS8V")
      (footprint "eagle-import:EXBS8V")
      (libsource (lib "eagle-import") (part "4R-NEXBS8V"))
    )
    (comp (ref "U7")
      (value "PCA9685PW,118")
      (footprint "eagle-import:SOP65P640X110-28N")
      (fields (field (name "MF") "NXP USA"))
      (libsource (lib "eagle-import") (part "PCA9685PW,118"))
    )
    (comp (ref "U9")
      (value "LMR51420")
      (footprint "eagle-import:SOT23-6")
      (libsource (lib "eagle-import") (part "LMR51420"))
    )
    (comp (ref "U10")
      (value "ST-M24256E-FMN6TP")
      (footprint "eagle-import:SO-8")
      (libsource (lib "eagle-import") (part "ST-M24256E-FMN6TP"))
    )
    (comp (ref "C3")
      (value "1u")
      (footprint "eagle-import:C1206")
      (libsource (lib "eagle-import") (part "rcl_334_C-EUC1206"))
    )
    (comp (ref "C4")
      (value "1u")
      (footprint "eagle-import:C1206")
      (libsource (lib "eagle-import") (part "rcl_334_C-EUC1206"))
    )
    (comp (ref "C5")
      (value "1u")
      (footprint "eagle-import:C1206")
      (libsource (lib "eagle-import") (part "rcl_334_C-EUC1206"))
    )
    (comp (ref "C9")
      (value "100p")
      (footprint "eagle-import:C0603")
      (libsource (lib "eagle-import") (part "rcl_334_C-EUC0603"))
    )
    (comp (ref "C10")
      (value "4u7")
      (footprint "eagle-import:C0603")
      (libsource (lib "eagle-import") (part "rcl_334_C-EUC0603"))
    )
    (comp (ref "C11")
      (value "4u7")
      (footprint "eagle-import:C0603")
      (libsource (lib "eagle-import") (part "rcl_334_C-EUC0603"))
    )
    (comp (ref "C19")
      (value "100n")
      (footprint "eagle-import:C0603")
      (libsource (lib "eagle-import") (part "rcl_334_C-EUC0603"))
    )
    (comp (ref "C20")
      (value "1u")
      (footprint "eagle-import:C0603")
      (libsource (lib "eagle-import") (part "rcl_334_C-EUC0603"))
    )
    (comp (ref "C25")
      (value "100n")
      (footprint "eagle-import:C0603")
      (libsource (lib "eagle-import") (part "rcl_334_C-EUC0603"))
    )
    (comp (ref "C58")
      (value "10p")
      (footprint "eagle-import:C0603")
      (libsource (lib "eagle-import") (part "rcl_334_C-EUC0603"))
    )
    (comp (ref "D11")
      (value "B2100")
      (footprint "eagle-import:SMB")
      (libsource (lib "eagle-import") (part "DIODE-SMB"))
    )
    (comp (ref "D13")
      (value "BZX84J")
      (footprint "eagle-import:SOD323")
      (libsource (lib "eagle-import") (part "BZX84J"))
    )
    (comp (ref "L2")
      (value "7447773101")
      (footprint "eagle-import:L_7.4X7.4")
      (libsource (lib "eagle-import") (part "POWER_INDUCTOR7.4X7.4"))
    )
    (comp (ref "Q1")
      (value "ZXMN6A08E6")
      (footprint "eagle-import:SOT23-6")
      (libsource (lib "eagle-import") (part "ZXMN6A08E6"))
    )
    (comp (ref "Q3")
      (value "IRLML0100TR")
      (footprint "eagle-import:SOT23")
      (libsource (lib "eagle-import") (part "IRLML0100TR"))
    )
    (comp (ref "Q4")
      (value "ZXMP3A17E6")
      (footprint "eagle-import:SOT23-6")
      (libsource (lib "eagle-import") (part "ZXMP3A17E6"))
    )
    (comp (ref "Q5")
      (value "ZXMP3A17E6")
      (footprint "eagle-import:SOT23-6")
      (libsource (lib "eagle-import") (part "ZXMP3A17E6"))
    )
    (comp (ref "R2")
      (value "0R56")
      (footprint "eagle-import:R0805")
      (libsource (lib "eagle-import") (part "rcl_334_R-EU_R0805"))
    )
    (comp (ref "R3")
      (value "0R56")
      (footprint "eagle-import:R0805")
      (libsource (lib "eagle-import") (part "rcl_334_R-EU_R0805"))
    )
    (comp (ref "R8")
      (value "10k")
      (footprint "eagle-import:R0603")
      (libsource (lib "eagle-import") (part "rcl_334_R-EU_R0603"))
    )
    (comp (ref "R12")
      (value "0R")
      (footprint "eagle-import:R0603")
      (libsource (lib "eagle-import") (part "rcl_334_R-EU_R0603"))
    )
    (comp (ref "R14")
      (value "10k")
      (footprint "eagle-import:R0603")
      (libsource (lib "eagle-import") (part "rcl_334_R-EU_R0603"))
    )
    (comp (ref "R18")
      (value "110k")
      (footprint "eagle-import:R0603")
      (libsource (lib "eagle-import") (part "rcl_334_R-EU_R0603"))
    )
    (comp (ref "R21")
      (value "39k")
      (footprint "eagle-import:R0603")
      (libsource (lib "eagle-import") (part "rcl_334_R-EU_R0603"))
    )
    (comp (ref "R22")
      (value "2R2")
      (footprint "eagle-import:R0603")
      (libsource (lib "eagle-import") (part "rcl_334_R-EU_R0603"))
    )
    (comp (ref "R32")
      (value "10k")
      (footprint "eagle-import:R0603")
      (libsource (lib "eagle-import") (part "rcl_334_R-EU_R0603"))
    )
    (comp (ref "R45")
      (value "1k")
      (footprint "eagle-import:R0603")
      (libsource (lib "eagle-import") (part "rcl_334_R-EU_R0603"))
    )
    (comp (ref "S6")
      (value "SWITCH-SPDT-PTH-11.6X4.0MM")
      (footprint "eagle-import:SWITCH_SPDT_PTH_11.6X4.0MM")
      (libsource (lib "eagle-import") (part "SWITCH-SPDT-PTH-11.6X4.0MM"))
    )
    (comp (ref "U6")
      (value "ZXLD1370Q")
      (footprint "eagle-import:TSSOP16E")
      (libsource (lib "eagle-import") (part "ZXLD1370Q"))
    )
    (comp (ref "C28")
      (value "100nF")
      (footprint "eagle-import:C0603")
      (libsource (lib "eagle-import") (part "rcl_334_C-EUC0603"))
    )
    (comp (ref "C29")
      (value "100nF")
      (footprint "eagle-import:C0603")
      (libsource (lib "eagle-import") (part "rcl_334_C-EUC0603"))
    )
    (comp (ref "C30")
      (value "100nF")
      (footprint "eagle-import:C0603")
      (libsource (lib "eagle-import") (part "rcl_334_C-EUC0603"))
    )
    (comp (ref "C33")
      (value "100nF")
      (footprint "eagle-import:C0603")
      (libsource (lib "eagle-import") (part "rcl_334_C-EUC0603"))
    )
    (comp (ref "C34")
      (value "100nF")
      (footprint "eagle-import:C0603")
      (libsource (lib "eagle-import") (part "rcl_334_C-EUC0603"))
    )
    (comp (ref "C35")
      (value "100nF")
      (footprint "eagle-import:C0603")
      (libsource (lib "eagle-import") (part "rcl_334_C-EUC0603"))
    )
    (comp (ref "C36")
      (value "100nF")
      (footprint "eagle-import:C0603")
      (libsource (lib "eagle-import") (part "rcl_334_C-EUC0603"))
    )
    (comp (ref "C37")
      (value "100nF")
      (footprint "eagle-import:C0603")
      (libsource (lib "eagle-import") (part "rcl_334_C-EUC0603"))
    )
    (comp (ref "C38")
      (value "100nF")
      (footprint "eagle-import:C0603")
      (libsource (lib "eagle-import") (part "rcl_334_C-EUC0603"))
    )
    (comp (ref "R20")
      (value "10k")
      (footprint "eagle-import:R0603")
      (libsource (lib "eagle-import") (part "R-EU_R0603"))
    )
    (comp (ref "R24")
      (value "10k")
      (footprint "eagle-import:R0603")
      (libsource (lib "eagle-import") (part "R-EU_R0603"))
    )
    (comp (ref "R25")
      (value "10k")
      (footprint "eagle-import:R0603")
      (libsource (lib "eagle-import") (part "R-EU_R0603"))
    )
    (comp (ref "R26")
      (value "10k")
      (footprint "eagle-import:R0603")
      (libsource (lib "eagle-import") (part "R-EU_R0603"))
    )
    (comp (ref "R27")
      (value "10k")
      (footprint "eagle-import:R0603")
      (libsource (lib "eagle-import") (part "R-EU_R0603"))
    )
    (comp (ref "R28")
      (value "10k")
      (footprint "eagle-import:R0603")
      (libsource (lib "eagle-import") (part "R-EU_R0603"))
    )
    (comp (ref "R29")
      (value "10k")
      (footprint "eagle-import:R0603")
      (libsource (lib "eagle-import") (part "R-EU_R0603"))
    )
    (comp (ref "R30")
      (value "10k")
      (footprint "eagle-import:R0603")
      (libsource (lib "eagle-import") (part "R-EU_R0603"))
    )
    (comp (ref "R31")
      (value "10k")
      (footprint "eagle-import:R0603")
      (libsource (lib "eagle-import") (part "R-EU_R0603"))
    )
    (comp (ref "S1")
      (value "SWITCH-SPDT-PTH-11.6X4.0MM")
      (footprint "eagle-import:SWITCH_SPDT_PTH_11.6X4.0MM")
      (libsource (lib "eagle-import") (part "SWITCH-SPDT-PTH-11.6X4.0MM"))
    )
    (comp (ref "S2")
      (value "MOMENTARY-SWITCH-SPST-PTH-6.0MM")
      (footprint "eagle-import:TACTILE_SWITCH_PTH_6.0MM")
      (libsource (lib "eagle-import") (part "MOMENTARY-SWITCH-SPST-PTH-6.0MM"))
    )
    (comp (ref "S3")
      (value "SWS001")
      (footprint "eagle-import:SMS-001")
      (libsource (lib "eagle-import") (part "SWS001"))
    )
    (comp (ref "X1")
      (value "ENODER_ROTARY")
      (footprint "eagle-import:ENCODER")
      (libsource (lib "eagle-import") (part "ENODER_ROTARY"))
    )
    (comp (ref "X3")
      (value "ENCODER-2")
      (footprint "eagle-import:ENCODER-2")
      (libsource (lib "eagle-import") (part "ENCODER-2"))
    )
    (comp (ref "C50")
      (value "10u")
      (footprint "eagle-import:C0805")
      (libsource (lib "eagle-import") (part "rcl_334_C-EUC0805"))
    )
    (comp (ref "C51")
      (value "1u")
      (footprint "eagle-import:C0805")
      (libsource (lib "eagle-import") (part "rcl_334_C-EUC0805"))
    )
    (comp (ref "C52")
      (value "10u")
      (footprint "eagle-import:C0805")
      (libsource (lib "eagle-import") (part "rcl_334_C-EUC0805"))
    )
    (comp (ref "C53")
      (value "1u")
      (footprint "eagle-import:C0805")
      (libsource (lib "eagle-import") (part "rcl_334_C-EUC0805"))
    )
    (comp (ref "D12")
      (value "PMEG6002EJ115")
      (footprint "eagle-import:SOD323-R")
      (libsource (lib "eagle-import") (part "DIODE-SOD323-R"))
    )
    (comp (ref "D14")
      (value "PMEG6002EJ115")
      (footprint "eagle-import:SOD323-R")
      (libsource (lib "eagle-import") (part "DIODE-SOD323-R"))
    )
    (comp (ref "D17")
      (value "BZX84J")
      (footprint "eagle-import:SOD323")
      (libsource (lib "eagle-import") (part "BZX84J"))
    )
    (comp (ref "D18")
      (value "BZX84J")
      (footprint "eagle-import:SOD323")
      (libsource (lib "eagle-import") (part "BZX84J"))
    )
    (comp (ref "L8")
      (value "SRR4828A-101M")
      (footprint "eagle-import:L_5X5")
      (libsource (lib "eagle-import") (part "POWER_INDUCTOR5X5"))
    )
    (comp (ref "L9")
      (value "SRR4828A-101M")
      (footprint "eagle-import:L_5X5")
      (libsource (lib "eagle-import") (part "POWER_INDUCTOR5X5"))
    )
    (comp (ref "Q9")
      (value "ZXMP3A17E6")
      (footprint "eagle-import:SOT23-6")
      (libsource (lib "eagle-import") (part "ZXMP3A17E6"))
    )
    (comp (ref "Q10")
      (value "ZXMP3A17E6")
      (footprint "eagle-import:SOT23-6")
      (libsource (lib "eagle-import") (part "ZXMP3A17E6"))
    )
    (comp (ref "R37")
      (value "1R05")
      (footprint "eagle-import:R0805")
      (libsource (lib "eagle-import") (part "rcl_334_R-EU_R0805"))
    )
    (comp (ref "R38")
      (value "1R43")
      (footprint "eagle-import:R0805")
      (libsource (lib "eagle-import") (part "rcl_334_R-EU_R0805"))
    )
    (comp (ref "R41")
      (value "10k")
      (footprint "eagle-import:R0603")
      (libsource (lib "eagle-import") (part "rcl_334_R-EU_R0603"))
    )
    (comp (ref "R42")
      (value "10k")
      (footprint "eagle-import:R0603")
      (libsource (lib "eagle-import") (part "rcl_334_R-EU_R0603"))
    )
    (comp (ref "U11")
      (value "AP3031")
      (footprint "eagle-import:SOT23-6")
      (libsource (lib "eagle-import") (part "AP3031"))
    )
    (comp (ref "U12")
      (value "AP3031")
      (footprint "eagle-import:SOT23-6")
      (libsource (lib "eagle-import") (part "AP3031"))
    )
    (comp (ref "C27")
      (value "100nF")
      (footprint "eagle-import:C0603")
      (libsource (lib "eagle-import") (part "C-EUC0603"))
    )
    (comp (ref "C31")
      (value "15pF")
      (footprint "eagle-import:C0603")
      (libsource (lib "eagle-import") (part "rcl_334_C-EUC0603"))
    )
    (comp (ref "C32")
      (value "100nF")
      (footprint "eagle-import:C0603")
      (libsource (lib "eagle-import") (part "rcl_334_C-EUC0603"))
    )
    (comp (ref "C40")
      (value "100nF")
      (footprint "eagle-import:C0603")
      (libsource (lib "eagle-import") (part "rcl_334_C-EUC0603"))
    )
    (comp (ref "C41")
      (value "10uF/6.3V")
      (footprint "eagle-import:CT3216")
      (libsource (lib "eagle-import") (part "CPOL-EUCT3216"))
    )
    (comp (ref "C46")
      (value "100nF")
      (footprint "eagle-import:C0603")
      (libsource (lib "eagle-import") (part "rcl_334_C-EUC0603"))
    )
    (comp (ref "C47")
      (value "100nF")
      (footprint "eagle-import:C0603")
      (libsource (lib "eagle-import") (part "rcl_334_C-EUC0603"))
    )
    (comp (ref "C48")
      (value "100nF")
      (footprint "eagle-import:C0603")
      (libsource (lib "eagle-import") (part "rcl_334_C-EUC0603"))
    )
    (comp (ref "R16")
      (value "1k")
      (footprint "eagle-import:R0603")
      (libsource (lib "eagle-import") (part "R-EU_R0603"))
    )
    (comp (ref "R17")
      (value "10k")
      (footprint "eagle-import:R0603")
      (libsource (lib "eagle-import") (part "R-EU_R0603"))
    )
    (comp (ref "U8")
      (value "PIC32MX120F064H")
      (footprint "eagle-import:PIC32MX-TQFN")
      (libsource (lib "eagle-import") (part "PIC32MX120F064H"))
    )
    (comp (ref "X2")
      (value "BM05B-PASS")
      (footprint "eagle-import:BM05B-PASS")
      (libsource (lib "eagle-import") (part "BM05B-PASS"))
    )
    (comp (ref "Y1")
      (value "MCSJK-3N-8.00-3.3-25-B")
      (footprint "eagle-import:WE-SPXO_CFPS-104")
      (libsource (lib "eagle-import") (part "WE-SPXO_CFPS-104_830205028309"))
    )
    (comp (ref "C21")
      (value "10u")
      (footprint "eagle-import:C0805")
      (libsource (lib "eagle-import") (part "rcl_334_C-EUC0805"))
    )
    (comp (ref "C22")
      (value "1u")
      (footprint "eagle-import:C0805")
      (libsource (lib "eagle-import") (part "rcl_334_C-EUC0805"))
    )
    (comp (ref "C23")
      (value "10u")
      (footprint "eagle-import:C0805")
      (libsource (lib "eagle-import") (part "rcl_334_C-EUC0805"))
    )
    (comp (ref "C24")
      (value "1u")
      (footprint "eagle-import:C0805")
      (libsource (lib "eagle-import") (part "rcl_334_C-EUC0805"))
    )
    (comp (ref "D5")
      (value "PMEG6002EJ115")
      (footprint "eagle-import:SOD323-R")
      (libsource (lib "eagle-import") (part "DIODE-SOD323-R"))
    )
    (comp (ref "D6")
      (value "PMEG6002EJ115")
      (footprint "eagle-import:SOD323-R")
      (libsource (lib "eagle-import") (part "DIODE-SOD323-R"))
    )
    (comp (ref "L5")
      (value "SRR4828A-101M")
      (footprint "eagle-import:L_5X5")
      (libsource (lib "eagle-import") (part "POWER_INDUCTOR5X5"))
    )
    (comp (ref "L6")
      (value "SRR4828A-101M")
      (footprint "eagle-import:L_5X5")
      (libsource (lib "eagle-import") (part "POWER_INDUCTOR5X5"))
    )
    (comp (ref "R10")
      (value "4R")
      (footprint "eagle-import:R0805")
      (libsource (lib "eagle-import") (part "rcl_334_R-EU_R0805"))
    )
    (comp (ref "R11")
      (value "4R")
      (footprint "eagle-import:R0805")
      (libsource (lib "eagle-import") (part "rcl_334_R-EU_R0805"))
    )
    (comp (ref "U4")
      (value "AP3031")
      (footprint "eagle-import:SOT23-6")
      (libsource (lib "eagle-import") (part "AP3031"))
    )
    (comp (ref "U5")
      (value "AP3031")
      (footprint "eagle-import:SOT23-6")
      (libsource (lib "eagle-import") (part "AP3031"))
    )
    (comp (ref "JP1")
      (value "PINHD-1X4")
      (footprint "eagle-import:1X04")
      (libsource (lib "eagle-import") (part "PINHD-1X4"))
    )
    (comp (ref "JP2")
      (value "PINHD-1X8")
      (footprint "eagle-import:1X08")
      (libsource (lib "eagle-import") (part "PINHD-1X8"))
    )
    (comp (ref "JP3")
      (value "PINHD-1X11")
      (footprint "eagle-import:1X11")
      (libsource (lib "eagle-import") (part "PINHD-1X11"))
    )
    (comp (ref "JP5")
      (value "PINHD-1X8")
      (footprint "eagle-import:1X08")
      (libsource (lib "eagle-import") (part "PINHD-1X8"))
    )
    (comp (ref "C6")
      (value "100p")
      (footprint "eagle-import:C0603")
      (libsource (lib "eagle-import") (part "rcl_334_C-EUC0603"))
    )
    (comp (ref "C7")
      (value "4u7")
      (footprint "eagle-import:C0603")
      (libsource (lib "eagle-import") (part "rcl_334_C-EUC0603"))
    )
    (comp (ref "C8")
      (value "4u7")
      (footprint "eagle-import:C0603")
      (libsource (lib "eagle-import") (part "rcl_334_C-EUC0603"))
    )
    (comp (ref "C13")
      (value "1u")
      (footprint "eagle-import:C0603")
      (libsource (lib "eagle-import") (part "rcl_334_C-EUC0603"))
    )
    (comp (ref "C14")
      (value "100n")
      (footprint "eagle-import:C0603")
      (libsource (lib "eagle-import") (part "rcl_334_C-EUC0603"))
    )
    (comp (ref "C16")
      (value "1u")
      (footprint "eagle-import:C1206")
      (libsource (lib "eagle-import") (part "rcl_334_C-EUC1206"))
    )
    (comp (ref "C17")
      (value "1u")
      (footprint "eagle-import:C1206")
      (libsource (lib "eagle-import") (part "rcl_334_C-EUC1206"))
    )
    (comp (ref "C18")
      (value "1u")
      (footprint "eagle-import:C1206")
      (libsource (lib "eagle-import") (part "rcl_334_C-EUC1206"))
    )
    (comp (ref "C26")
      (value "10p")
      (footprint "eagle-import:C0603")
      (libsource (lib "eagle-import") (part "rcl_334_C-EUC0603"))
    )
    (comp (ref "D3")
      (value "B2100")
      (footprint "eagle-import:SMB")
      (libsource (lib "eagle-import") (part "DIODE-SMB"))
    )
    (comp (ref "D8")
      (value "BZX84J")
      (footprint "eagle-import:SOD323")
      (libsource (lib "eagle-import") (part "BZX84J"))
    )
    (comp (ref "L3")
      (value "470u")
      (footprint "eagle-import:L_7.4X7.4")
      (libsource (lib "eagle-import") (part "POWER_INDUCTOR7.4X7.4"))
    )
    (comp (ref "Q2")
      (value "ZXMN6A08E6")
      (footprint "eagle-import:SOT23-6")
      (libsource (lib "eagle-import") (part "ZXMN6A08E6"))
    )
    (comp (ref "Q7")
      (value "ZXMP3A17E6")
      (footprint "eagle-import:SOT23-6")
      (libsource (lib "eagle-import") (part "ZXMP3A17E6"))
    )
    (comp (ref "R4")
      (value "68k")
      (footprint "eagle-import:R0603")
      (libsource (lib "eagle-import") (part "rcl_334_R-EU_R0603"))
    )
    (comp (ref "R5")
      (value "2R2")
      (footprint "eagle-import:R0805")
      (libsource (lib "eagle-import") (part "rcl_334_R-EU_R0805"))
    )
    (comp (ref "R6")
      (value "22k")
      (footprint "eagle-import:R0603")
      (libsource (lib "eagle-import") (part "rcl_334_R-EU_R0603"))
    )
    (comp (ref "R7")
      (value "2R2")
      (footprint "eagle-import:R0603")
      (libsource (lib "eagle-import") (part "rcl_334_R-EU_R0603"))
    )
    (comp (ref "R9")
      (value "2R2")
      (footprint "eagle-import:R0805")
      (libsource (lib "eagle-import") (part "rcl_334_R-EU_R0805"))
    )
    (comp (ref "R13")
      (value "1k")
      (footprint "eagle-import:R0603")
      (libsource (lib "eagle-import") (part "rcl_334_R-EU_R0603"))
    )
    (comp (ref "R15")
      (value "10k")
      (footprint "eagle-import:R0603")
      (libsource (lib "eagle-import") (part "rcl_334_R-EU_R0603"))
    )
    (comp (ref "R55")
      (value "10k")
      (footprint "eagle-import:R0603")
      (libsource (lib "eagle-import") (part "rcl_334_R-EU_R0603"))
    )
    (comp (ref "S4")
      (value "SWITCH-SPDT-PTH-11.6X4.0MM")
      (footprint "eagle-import:SWITCH_SPDT_PTH_11.6X4.0MM")
      (libsource (lib "eagle-import") (part "SWITCH-SPDT-PTH-11.6X4.0MM"))
    )
    (comp (ref "T3")
      (value "2N7002A")
      (footprint "eagle-import:SOT-23")
      (libsource (lib "eagle-import") (part "NMOSSOT23"))
    )
    (comp (ref "U2")
      (value "ZXLD1370Q")
      (footprint "eagle-import:TSSOP16E")
      (libsource (lib "eagle-import") (part "ZXLD1370Q"))
    )
  )
  (nets
    (net (code "1") (name "3,3V") (class "Default")
      (node (ref "C32") (pin "1") (pinfunction "1_1") (pintype "passive"))
      (node (ref "C39") (pin "1") (pinfunction "1_1") (pintype "passive"))
      (node (ref "C40") (pin "1") (pinfunction "1_1") (pintype "passive"))
      (node (ref "C44") (pin "2") (pinfunction "2_2") (pintype "passive"))
      (node (ref "C45") (pin "2") (pinfunction "2_2") (pintype "passive"))
      (node (ref "C46") (pin "1") (pinfunction "1_1") (pintype "passive"))
      (node (ref "C47") (pin "1") (pinfunction "1_1") (pintype "passive"))
      (node (ref "C48") (pin "1") (pinfunction "1_1") (pintype "passive"))
      (node (ref "C49") (pin "1") (pinfunction "1_1") (pintype "passive"))
      (node (ref "JP1") (pin "1") (pinfunction "1_1") (pintype "passive"))
      (node (ref "L7") (pin "2") (pinfunction "2_2") (pintype "passive"))
      (node (ref "R17") (pin "1") (pinfunction "1_1") (pintype "passive"))
      (node (ref "R20") (pin "1") (pinfunction "1_1") (pintype "passive"))
      (node (ref "R24") (pin "1") (pinfunction "1_1") (pintype "passive"))
      (node (ref "R25") (pin "1") (pinfunction "1_1") (pintype "passive"))
      (node (ref "R26") (pin "1") (pinfunction "1_1") (pintype "passive"))
      (node (ref "R27") (pin "1") (pinfunction "1_1") (pintype "passive"))
      (node (ref "R28") (pin "1") (pinfunction "1_1") (pintype "passive"))
      (node (ref "R29") (pin "1") (pinfunction "1_1") (pintype "passive"))
      (node (ref "R30") (pin "1") (pinfunction "1_1") (pintype "passive"))
      (node (ref "R31") (pin "1") (pinfunction "1_1") (pintype "passive"))
      (node (ref "R33") (pin "1") (pinfunction "1_1") (pintype "passive"))
      (node (ref "R34") (pin "1") (pinfunction "1_1") (pintype "passive"))
      (node (ref "R52") (pin "1") (pinfunction "1_1") (pintype "passive"))
      (node (ref "U10") (pin "8") (pinfunction "VCC_8") (pintype "power_in"))
      (node (ref "U7") (pin "28") (pinfunction "VDD_28") (pintype "power_in"))
      (node (ref "U8") (pin "10") (pinfunction "VDD_10") (pintype "bidirectional"))
      (node (ref "U8") (pin "19") (pinfunction "AVDD_19") (pintype "bidirectional"))
      (node (ref "U8") (pin "26") (pinfunction "VDD_26") (pintype "bidirectional"))
      (node (ref "U8") (pin "38") (pinfunction "VDD_38") (pintype "bidirectional"))
      (node (ref "U8") (pin "57") (pinfunction "VDD_57") (pintype "bidirectional"))
      (node (ref "X2") (pin "P$5") (pinfunction "5_P$5") (pintype "bidirectional"))
      (node (ref "Y1") (pin "1") (pinfunction "SO_1") (pintype "input"))
      (node (ref "Y1") (pin "4") (pinfunction "+VS_4") (pintype "power_in"))
    )
    (net (code "2") (name "CHMSL") (class "Default")
      (node (ref "JP2") (pin "7") (pinfunction "7_7") (pintype "passive"))
      (node (ref "Q12") (pin "1") (pinfunction "D_1") (pintype "passive"))
      (node (ref "Q12") (pin "2") (pinfunction "D_2") (pintype "passive"))
      (node (ref "Q12") (pin "5") (pinfunction "D_5") (pintype "passive"))
      (node (ref "Q12") (pin "6") (pinfunction "D_6") (pintype "passive"))
    )
    (net (code "3") (name "CHMSL_A") (class "Default")
      (node (ref "C57") (pin "1") (pinfunction "1_1") (pintype "passive"))
      (node (ref "D16") (pin "C") (pinfunction "C_C") (pintype "passive"))
      (node (ref "JP5") (pin "8") (pinfunction "8_8") (pintype "passive"))
    )
    (net (code "4") (name "CHMSL_K") (class "Default")
      (node (ref "JP5") (pin "7") (pinfunction "7_7") (pintype "passive"))
      (node (ref "R40") (pin "1") (pinfunction "1_1") (pintype "passive"))
      (node (ref "U14") (pin "3") (pinfunction "FB_3") (pintype "input"))
    )
    (net (code "5") (name "CLOCK") (class "Default")
      (node (ref "C31") (pin "1") (pinfunction "1_1") (pintype "passive"))
      (node (ref "U8") (pin "39") (pinfunction "RC12_39") (pintype "bidirectional"))
      (node (ref "Y1") (pin "3") (pinfunction "OUT_3") (pintype "output"))
    )
    (net (code "6") (name "CTRL1") (class "Default")
      (node (ref "S7") (pin "C@1") (pinfunction "2_C@1") (pintype "bidirectional"))
      (node (ref "U3") (pin "4") (pinfunction "CTRL_4") (pintype "power_in"))
    )
    (net (code "7") (name "CTRL2") (class "Default")
      (node (ref "S7") (pin "C@2") (pinfunction "5_C@2") (pintype "bidirectional"))
      (node (ref "U1") (pin "4") (pinfunction "CTRL_4") (pintype "power_in"))
    )
    (net (code "8") (name "FLAG") (class "Default")
      (node (ref "U2") (pin "14") (pinfunction "FLAG_14") (pintype "power_in"))
    )
    (net (code "9") (name "FOG") (class "Default")
      (node (ref "JP2") (pin "4") (pinfunction "4_4") (pintype "passive"))
      (node (ref "Q9") (pin "1") (pinfunction "D_1") (pintype "passive"))
      (node (ref "Q9") (pin "2") (pinfunction "D_2") (pintype "passive"))
      (node (ref "Q9") (pin "5") (pinfunction "D_5") (pintype "passive"))
      (node (ref "Q9") (pin "6") (pinfunction "D_6") (pintype "passive"))
    )
    (net (code "10") (name "FOG_A") (class "Default")
      (node (ref "C51") (pin "1") (pinfunction "1_1") (pintype "passive"))
      (node (ref "D12") (pin "C") (pinfunction "C_C") (pintype "passive"))
      (node (ref "JP5") (pin "2") (pinfunction "2_2") (pintype "passive"))
    )
    (net (code "11") (name "FOG_K") (class "Default")
      (node (ref "JP5") (pin "1") (pinfunction "1_1") (pintype "passive"))
      (node (ref "R37") (pin "1") (pinfunction "1_1") (pintype "passive"))
      (node (ref "U11") (pin "3") (pinfunction "FB_3") (pintype "input"))
    )
    (net (code "12") (name "FREQ{slash}DUTY") (class "Default")
      (node (ref "C29") (pin "1") (pinfunction "1_1") (pintype "passive"))
      (node (ref "S1") (pin "2") (pinfunction "P_2") (pintype "passive"))
      (node (ref "U8") (pin "18") (pinfunction "RB7_18") (pintype "bidirectional"))
    )
    (net (code "13") (name "GND") (class "Default")
      (node (ref "C1") (pin "2") (pinfunction "2_2") (pintype "passive"))
      (node (ref "C10") (pin "1") (pinfunction "1_1") (pintype "passive"))
      (node (ref "C11") (pin "1") (pinfunction "1_1") (pintype "passive"))
      (node (ref "C12") (pin "2") (pinfunction "2_2") (pintype "passive"))
      (node (ref "C13") (pin "1") (pinfunction "1_1") (pintype "passive"))
      (node (ref "C14") (pin "1") (pinfunction "1_1") (pintype "passive"))
      (node (ref "C15") (pin "2") (pinfunction "2_2") (pintype "passive"))
      (node (ref "C16") (pin "1") (pinfunction "1_1") (pintype "passive"))
      (node (ref "C17") (pin "1") (pinfunction "1_1") (pintype "passive"))
      (node (ref "C18") (pin "1") (pinfunction "1_1") (pintype "passive"))
      (node (ref "C19") (pin "1") (pinfunction "1_1") (pintype "passive"))
      (node (ref "C2") (pin "2") (pinfunction "2_2") (pintype "passive"))
      (node (ref "C20") (pin "1") (pinfunction "1_1") (pintype "passive"))
      (node (ref "C21") (pin "2") (pinfunction "2_2") (pintype "passive"))
      (node (ref "C22") (pin "2") (pinfunction "2_2") (pintype "passive"))
      (node (ref "C23") (pin "2") (pinfunction "2_2") (pintype "passive"))
      (node (ref "C24") (pin "2") (pinfunction "2_2") (pintype "passive"))
      (node (ref "C26") (pin "1") (pinfunction "1_1") (pintype "passive"))
      (node (ref "C27") (pin "2") (pinfunction "2_2") (pintype "passive"))
      (node (ref "C28") (pin "2") (pinfunction "2_2") (pintype "passive"))
      (node (ref "C29") (pin "2") (pinfunction "2_2") (pintype "passive"))
      (node (ref "C3") (pin "1") (pinfunction "1_1") (pintype "passive"))
      (node (ref "C30") (pin "2") (pinfunction "2_2") (pintype "passive"))
      (node (ref "C31") (pin "2") (pinfunction "2_2") (pintype "passive"))
      (node (ref "C32") (pin "2") (pinfunction "2_2") (pintype "passive"))
      (node (ref "C33") (pin "2") (pinfunction "2_2") (pintype "passive"))
      (node (ref "C34") (pin "2") (pinfunction "2_2") (pintype "passive"))
      (node (ref "C35") (pin "2") (pinfunction "2_2") (pintype "passive"))
      (node (ref "C36") (pin "2") (pinfunction "2_2") (pintype "passive"))
      (node (ref "C37") (pin "2") (pinfunction "2_2") (pintype "passive"))
      (node (ref "C38") (pin "2") (pinfunction "2_2") (pintype "passive"))
      (node (ref "C39") (pin "2") (pinfunction "2_2") (pintype "passive"))
      (node (ref "C4") (pin "1") (pinfunction "1_1") (pintype "passive"))
      (node (ref "C40") (pin "2") (pinfunction "2_2") (pintype "passive"))
      (node (ref "C41") (pin "-") (pinfunction "-_-") (pintype "passive"))
      (node (ref "C43") (pin "1") (pinfunction "1_1") (pintype "passive"))
      (node (ref "C44") (pin "1") (pinfunction "1_1") (pintype "passive"))
      (node (ref "C45") (pin "1") (pinfunction "1_1") (pintype "passive"))
      (node (ref "C46") (pin "2") (pinfunction "2_2") (pintype "passive"))
      (node (ref "C47") (pin "2") (pinfunction "2_2") (pintype "passive"))
      (node (ref "C48") (pin "2") (pinfunction "2_2") (pintype "passive"))
      (node (ref "C49") (pin "2") (pinfunction "2_2") (pintype "passive"))
      (node (ref "C5") (pin "1") (pinfunction "1_1") (pintype "passive"))
      (node (ref "C50") (pin "2") (pinfunction "2_2") (pintype "passive"))
      (node (ref "C51") (pin "2") (pinfunction "2_2") (pintype "passive"))
      (node (ref "C52") (pin "2") (pinfunction "2_2") (pintype "passive"))
      (node (ref "C53") (pin "2") (pinfunction "2_2") (pintype "passive"))
      (node (ref "C54") (pin "2") (pinfunction "2_2") (pintype "passive"))
      (node (ref "C55") (pin "2") (pinfunction "2_2") (pintype "passive"))
      (node (ref "C56") (pin "2") (pinfunction "2_2") (pintype "passive"))
      (node (ref "C57") (pin "2") (pinfunction "2_2") (pintype "passive"))
      (node (ref "C58") (pin "1") (pinfunction "1_1") (pintype "passive"))
      (node (ref "C6") (pin "1") (pinfunction "1_1") (pintype "passive"))
      (node (ref "C7") (pin "1") (pinfunction "1_1") (pintype "passive"))
      (node (ref "C8") (pin "1") (pinfunction "1_1") (pintype "passive"))
      (node (ref "C9") (pin "1") (pinfunction "1_1") (pintype "passive"))
      (node (ref "JP1") (pin "2") (pinfunction "2_2") (pintype "passive"))
      (node (ref "JP3") (pin "4") (pinfunction "4_4") (pintype "passive"))
      (node (ref "Q1") (pin "4") (pinfunction "S_4") (pintype "passive"))
      (node (ref "Q2") (pin "4") (pinfunction "S_4") (pintype "passive"))
      (node (ref "Q3") (pin "2") (pinfunction "S_2") (pintype "passive"))
      (node (ref "R1") (pin "2") (pinfunction "2_2") (pintype "passive"))
      (node (ref "R10") (pin "2") (pinfunction "2_2") (pintype "passive"))
      (node (ref "R11") (pin "2") (pinfunction "2_2") (pintype "passive"))
      (node (ref "R15") (pin "1") (pinfunction "1_1") (pintype "passive"))
      (node (ref "R19") (pin "2") (pinfunction "2_2") (pintype "passive"))
      (node (ref "R21") (pin "2") (pinfunction "2_2") (pintype "passive"))
      (node (ref "R32") (pin "2") (pinfunction "2_2") (pintype "passive"))
      (node (ref "R37") (pin "2") (pinfunction "2_2") (pintype "passive"))
      (node (ref "R38") (pin "2") (pinfunction "2_2") (pintype "passive"))
      (node (ref "R39") (pin "2") (pinfunction "2_2") (pintype "passive"))
      (node (ref "R40") (pin "2") (pinfunction "2_2") (pintype "passive"))
      (node (ref "R41") (pin "2") (pinfunction "2_2") (pintype "passive"))
      (node (ref "R42") (pin "2") (pinfunction "2_2") (pintype "passive"))
      (node (ref "R43") (pin "2") (pinfunction "2_2") (pintype "passive"))
      (node (ref "R44") (pin "2") (pinfunction "2_2") (pintype "passive"))
      (node (ref "R53") (pin "2") (pinfunction "2_2") (pintype "passive"))
      (node (ref "R54") (pin "2") (pinfunction "2_2") (pintype "passive"))
      (node (ref "R55") (pin "2") (pinfunction "2_2") (pintype "passive"))
      (node (ref "R56") (pin "2") (pinfunction "2_2") (pintype "passive"))
      (node (ref "R6") (pin "2") (pinfunction "2_2") (pintype "passive"))
      (node (ref "S1") (pin "3") (pinfunction "S_3") (pintype "passive"))
      (node (ref "T3") (pin "2") (pinfunction "S_2") (pintype "passive"))
      (node (ref "U1") (pin "2") (pinfunction "GND_2") (pintype "bidirectional"))
      (node (ref "U10") (pin "4") (pinfunction "VSS_4") (pintype "input"))
      (node (ref "U10") (pin "EP") (pinfunction "VSS_EP") (pintype "input"))
      (node (ref "U11") (pin "2") (pinfunction "GND_2") (pintype "bidirectional"))
      (node (ref "U12") (pin "2") (pinfunction "GND_2") (pintype "bidirectional"))
      (node (ref "U13") (pin "2") (pinfunction "GND_2") (pintype "bidirectional"))
      (node (ref "U14") (pin "2") (pinfunction "GND_2") (pintype "bidirectional"))
      (node (ref "U2") (pin "6") (pinfunction "SGND_6") (pintype "bidirectional"))
      (node (ref "U2") (pin "7") (pinfunction "PGND_7") (pintype "bidirectional"))
      (node (ref "U2") (pin "EXP") (pinfunction "PGND_EXP") (pintype "bidirectional"))
      (node (ref "U3") (pin "2") (pinfunction "GND_2") (pintype "bidirectional"))
      (node (ref "U4") (pin "2") (pinfunction "GND_2") (pintype "bidirectional"))
      (node (ref "U5") (pin "2") (pinfunction "GND_2") (pintype "bidirectional"))
      (node (ref "U6") (pin "6") (pinfunction "SGND_6") (pintype "bidirectional"))
      (node (ref "U6") (pin "7") (pinfunction "PGND_7") (pintype "bidirectional"))
      (node (ref "U6") (pin "EXP") (pinfunction "PGND_EXP") (pintype "bidirectional"))
      (node (ref "U7") (pin "1") (pinfunction "A0_1") (pintype "input"))
      (node (ref "U7") (pin "14") (pinfunction "VSS_14") (pintype "passive"))
      (node (ref "U7") (pin "2") (pinfunction "A1_2") (pintype "input"))
      (node (ref "U7") (pin "24") (pinfunction "A5_24") (pintype "input"))
      (node (ref "U7") (pin "3") (pinfunction "A2_3") (pintype "input"))
      (node (ref "U7") (pin "4") (pinfunction "A3_4") (pintype "input"))
      (node (ref "U7") (pin "5") (pinfunction "A4_5") (pintype "input"))
      (node (ref "U8") (pin "20") (pinfunction "AVSS_20") (pintype "bidirectional"))
      (node (ref "U8") (pin "25") (pinfunction "VSS_25") (pintype "bidirectional"))
      (node (ref "U8") (pin "41") (pinfunction "VSS_41") (pintype "bidirectional"))
      (node (ref "U8") (pin "9") (pinfunction "VSS_9") (pintype "bidirectional"))
      (node (ref "U9") (pin "1") (pinfunction "GND_1") (pintype "bidirectional"))
      (node (ref "X1") (pin "P$3") (pinfunction "GND_P$3") (pintype "bidirectional"))
      (node (ref "X2") (pin "P$1") (pinfunction "1_P$1") (pintype "bidirectional"))
      (node (ref "X3") (pin "P$2") (pinfunction "GND_P$2") (pintype "bidirectional"))
      (node (ref "Y1") (pin "2") (pinfunction "GND_2") (pintype "power_in"))
    )
    (net (code "14") (name "LET") (class "Default")
      (node (ref "JP2") (pin "6") (pinfunction "6_6") (pintype "passive"))
      (node (ref "Q11") (pin "1") (pinfunction "D_1") (pintype "passive"))
      (node (ref "Q11") (pin "2") (pinfunction "D_2") (pintype "passive"))
      (node (ref "Q11") (pin "5") (pinfunction "D_5") (pintype "passive"))
      (node (ref "Q11") (pin "6") (pinfunction "D_6") (pintype "passive"))
    )
    (net (code "15") (name "LET_A") (class "Default")
      (node (ref "C55") (pin "1") (pinfunction "1_1") (pintype "passive"))
      (node (ref "D15") (pin "C") (pinfunction "C_C") (pintype "passive"))
      (node (ref "JP5") (pin "4") (pinfunction "4_4") (pintype "passive"))
    )
    (net (code "16") (name "LET_K") (class "Default")
      (node (ref "JP5") (pin "3") (pinfunction "3_3") (pintype "passive"))
      (node (ref "R39") (pin "1") (pinfunction "1_1") (pintype "passive"))
      (node (ref "U13") (pin "3") (pinfunction "FB_3") (pintype "input"))
    )
    (net (code "17") (name "LOCK") (class "Default")
      (node (ref "C30") (pin "1") (pinfunction "1_1") (pintype "passive"))
      (node (ref "S3") (pin "2") (pinfunction "2_2") (pintype "passive"))
      (node (ref "U8") (pin "17") (pinfunction "RB6_17") (pintype "bidirectional"))
    )
    (net (code "18") (name "Net-(C26-Pad2)") (class "Default")
      (node (ref "C26") (pin "2") (pinfunction "2_2") (pintype "passive"))
      (node (ref "R13") (pin "1") (pinfunction "1_1") (pintype "passive"))
    )
    (net (code "19") (name "Net-(C27-Pad1)") (class "Default")
      (node (ref "C27") (pin "1") (pinfunction "1_1") (pintype "passive"))
      (node (ref "R16") (pin "1") (pinfunction "1_1") (pintype "passive"))
      (node (ref "R17") (pin "2") (pinfunction "2_2") (pintype "passive"))
    )
    (net (code "20") (name "Net-(C58-Pad2)") (class "Default")
      (node (ref "C58") (pin "2") (pinfunction "2_2") (pintype "passive"))
      (node (ref "R45") (pin "1") (pinfunction "1_1") (pintype "passive"))
    )
    (net (code "21") (name "Net-(D3-PadA)") (class "Default")
      (node (ref "D3") (pin "A") (pinfunction "A_A") (pintype "passive"))
      (node (ref "L3") (pin "2") (pinfunction "2_2") (pintype "passive"))
      (node (ref "Q2") (pin "1") (pinfunction "D_1") (pintype "passive"))
      (node (ref "Q2") (pin "2") (pinfunction "D_2") (pintype "passive"))
      (node (ref "Q2") (pin "5") (pinfunction "D_5") (pintype "passive"))
      (node (ref "Q2") (pin "6") (pinfunction "D_6") (pintype "passive"))
      (node (ref "R13") (pin "2") (pinfunction "2_2") (pintype "passive"))
    )
    (net (code "22") (name "Net-(D11-PadA)") (class "Default")
      (node (ref "D11") (pin "A") (pinfunction "A_A") (pintype "passive"))
      (node (ref "L2") (pin "2") (pinfunction "2_2") (pintype "passive"))
      (node (ref "Q1") (pin "1") (pinfunction "D_1") (pintype "passive"))
      (node (ref "Q1") (pin "2") (pinfunction "D_2") (pintype "passive"))
      (node (ref "Q1") (pin "5") (pinfunction "D_5") (pintype "passive"))
      (node (ref "Q1") (pin "6") (pinfunction "D_6") (pintype "passive"))
      (node (ref "R45") (pin "2") (pinfunction "2_2") (pintype "passive"))
    )
    (net (code "23") (name "Net-(Q1-G)") (class "Default")
      (node (ref "Q1") (pin "3") (pinfunction "G_3") (pintype "passive"))
      (node (ref "R22") (pin "2") (pinfunction "2_2") (pintype "passive"))
    )
    (net (code "24") (name "Net-(Q2-G)") (class "Default")
      (node (ref "Q2") (pin "3") (pinfunction "G_3") (pintype "passive"))
      (node (ref "R7") (pin "2") (pinfunction "2_2") (pintype "passive"))
    )
    (net (code "25") (name "Net-(Q3-D)") (class "Default")
      (node (ref "Q3") (pin "3") (pinfunction "D_3") (pintype "passive"))
      (node (ref "R12") (pin "1") (pinfunction "1_1") (pintype "passive"))
    )
    (net (code "26") (name "Net-(Q3-G)") (class "Default")
      (node (ref "Q3") (pin "1") (pinfunction "G_1") (pintype "passive"))
      (node (ref "S6") (pin "2") (pinfunction "P_2") (pintype "passive"))
    )
    (net (code "27") (name "Net-(Q4-G)") (class "Default")
      (node (ref "C25") (pin "2") (pinfunction "2_2") (pintype "passive"))
      (node (ref "Q4") (pin "3") (pinfunction "G_3") (pintype "passive"))
      (node (ref "R12") (pin "2") (pinfunction "2_2") (pintype "passive"))
      (node (ref "R14") (pin "1") (pinfunction "1_1") (pintype "passive"))
    )
    (net (code "28") (name "Net-(Q5-G)") (class "Default")
      (node (ref "D13") (pin "A") (pinfunction "A_A") (pintype "passive"))
      (node (ref "Q5") (pin "3") (pinfunction "G_3") (pintype "passive"))
      (node (ref "R32") (pin "1") (pinfunction "1_1") (pintype "passive"))
    )
    (net (code "29") (name "Net-(Q6-G)") (class "Default")
      (node (ref "D7") (pin "A") (pinfunction "A_A") (pintype "passive"))
      (node (ref "Q6") (pin "3") (pinfunction "G_3") (pintype "passive"))
      (node (ref "R54") (pin "1") (pinfunction "1_1") (pintype "passive"))
    )
    (net (code "30") (name "Net-(Q7-G)") (class "Default")
      (node (ref "D8") (pin "A") (pinfunction "A_A") (pintype "passive"))
      (node (ref "Q7") (pin "3") (pinfunction "G_3") (pintype "passive"))
      (node (ref "R55") (pin "1") (pinfunction "1_1") (pintype "passive"))
    )
    (net (code "31") (name "Net-(Q8-G)") (class "Default")
      (node (ref "D9") (pin "A") (pinfunction "A_A") (pintype "passive"))
      (node (ref "Q8") (pin "3") (pinfunction "G_3") (pintype "passive"))
      (node (ref "R56") (pin "1") (pinfunction "1_1") (pintype "passive"))
    )
    (net (code "32") (name "Net-(Q8-S)") (class "Default")
      (node (ref "C43") (pin "2") (pinfunction "2_2") (pintype "passive"))
      (node (ref "D9") (pin "C") (pinfunction "C_C") (pintype "passive"))
      (node (ref "Q8") (pin "4") (pinfunction "S_4") (pintype "passive"))
      (node (ref "U9") (pin "3") (pinfunction "VIN_3") (pintype "bidirectional"))
      (node (ref "U9") (pin "5") (pinfunction "EN_5") (pintype "bidirectional"))
    )
    (net (code "33") (name "Net-(Q9-G)") (class "Default")
      (node (ref "D17") (pin "A") (pinfunction "A_A") (pintype "passive"))
      (node (ref "Q9") (pin "3") (pinfunction "G_3") (pintype "passive"))
      (node (ref "R41") (pin "1") (pinfunction "1_1") (pintype "passive"))
    )
    (net (code "34") (name "Net-(Q10-G)") (class "Default")
      (node (ref "D18") (pin "A") (pinfunction "A_A") (pintype "passive"))
      (node (ref "Q10") (pin "3") (pinfunction "G_3") (pintype "passive"))
      (node (ref "R42") (pin "1") (pinfunction "1_1") (pintype "passive"))
    )
    (net (code "35") (name "Net-(Q11-G)") (class "Default")
      (node (ref "D19") (pin "A") (pinfunction "A_A") (pintype "passive"))
      (node (ref "Q11") (pin "3") (pinfunction "G_3") (pintype "passive"))
      (node (ref "R43") (pin "1") (pinfunction "1_1") (pintype "passive"))
    )
    (net (code "36") (name "Net-(Q12-G)") (class "Default")
      (node (ref "D20") (pin "A") (pinfunction "A_A") (pintype "passive"))
      (node (ref "Q12") (pin "3") (pinfunction "G_3") (pintype "passive"))
      (node (ref "R44") (pin "1") (pinfunction "1_1") (pintype "passive"))
    )
    (net (code "37") (name "Net-(R20-Pad2)") (class "Default")
      (node (ref "R20") (pin "2") (pinfunction "2_2") (pintype "passive"))
      (node (ref "S3") (pin "1") (pinfunction "1_1") (pintype "passive"))
    )
    (net (code "38") (name "Net-(R31-Pad2)") (class "Default")
      (node (ref "R31") (pin "2") (pinfunction "2_2") (pintype "passive"))
      (node (ref "S2") (pin "1") (pinfunction "1_1") (pintype "passive"))
    )
    (net (code "39") (name "Net-(RN1A-2)") (class "Default")
      (node (ref "RN1") (pin "8") (pinfunction "2_8") (pintype "passive"))
      (node (ref "U7") (pin "6") (pinfunction "LED0_6") (pintype "output"))
    )
    (net (code "40") (name "Net-(RN1B-2)") (class "Default")
      (node (ref "RN1") (pin "7") (pinfunction "2_7") (pintype "passive"))
      (node (ref "U7") (pin "7") (pinfunction "LED1_7") (pintype "output"))
    )
    (net (code "41") (name "Net-(RN1C-2)") (class "Default")
      (node (ref "RN1") (pin "6") (pinfunction "2_6") (pintype "passive"))
      (node (ref "U7") (pin "8") (pinfunction "LED2_8") (pintype "output"))
    )
    (net (code "42") (name "Net-(RN1D-2)") (class "Default")
      (node (ref "RN1") (pin "5") (pinfunction "2_5") (pintype "passive"))
      (node (ref "U7") (pin "9") (pinfunction "LED3_9") (pintype "output"))
    )
    (net (code "43") (name "Net-(RN2A-2)") (class "Default")
      (node (ref "RN2") (pin "8") (pinfunction "2_8") (pintype "passive"))
      (node (ref "U7") (pin "10") (pinfunction "LED4_10") (pintype "output"))
    )
    (net (code "44") (name "Net-(RN2B-2)") (class "Default")
      (node (ref "RN2") (pin "7") (pinfunction "2_7") (pintype "passive"))
      (node (ref "U7") (pin "11") (pinfunction "LED5_11") (pintype "output"))
    )
    (net (code "45") (name "Net-(RN2C-2)") (class "Default")
      (node (ref "RN2") (pin "6") (pinfunction "2_6") (pintype "passive"))
      (node (ref "U7") (pin "12") (pinfunction "LED6_12") (pintype "output"))
    )
    (net (code "46") (name "Net-(RN2D-2)") (class "Default")
      (node (ref "RN2") (pin "5") (pinfunction "2_5") (pintype "passive"))
      (node (ref "U7") (pin "13") (pinfunction "LED7_13") (pintype "output"))
    )
    (net (code "47") (name "Net-(RN3B-1)") (class "Default")
      (node (ref "RN3") (pin "2") (pinfunction "1_2") (pintype "passive"))
      (node (ref "U7") (pin "20") (pinfunction "LED13_20") (pintype "output"))
    )
    (net (code "48") (name "Net-(RN3C-1)") (class "Default")
      (node (ref "RN3") (pin "3") (pinfunction "1_3") (pintype "passive"))
      (node (ref "U7") (pin "21") (pinfunction "LED14_21") (pintype "output"))
    )
    (net (code "49") (name "Net-(RN3D-1)") (class "Default")
      (node (ref "RN3") (pin "4") (pinfunction "1_4") (pintype "passive"))
      (node (ref "U7") (pin "22") (pinfunction "LED15_22") (pintype "output"))
    )
    (net (code "50") (name "Net-(RN4B-1)") (class "Default")
      (node (ref "RN4") (pin "2") (pinfunction "1_2") (pintype "passive"))
      (node (ref "U7") (pin "18") (pinfunction "LED11_18") (pintype "output"))
    )
    (net (code "51") (name "Net-(RN4C-1)") (class "Default")
      (node (ref "RN4") (pin "3") (pinfunction "1_3") (pintype "passive"))
      (node (ref "U7") (pin "17") (pinfunction "LED10_17") (pintype "output"))
    )
    (net (code "52") (name "Net-(RN4D-1)") (class "Default")
      (node (ref "RN4") (pin "4") (pinfunction "1_4") (pintype "passive"))
      (node (ref "U7") (pin "16") (pinfunction "LED9_16") (pintype "output"))
    )
    (net (code "53") (name "Net-(S1-O)") (class "Default")
      (node (ref "R30") (pin "2") (pinfunction "2_2") (pintype "passive"))
      (node (ref "S1") (pin "1") (pinfunction "O_1") (pintype "passive"))
    )
    (net (code "54") (name "Net-(S4-P)") (class "Default")
      (node (ref "C13") (pin "2") (pinfunction "2_2") (pintype "passive"))
      (node (ref "C14") (pin "2") (pinfunction "2_2") (pintype "passive"))
      (node (ref "C7") (pin "2") (pinfunction "2_2") (pintype "passive"))
      (node (ref "R5") (pin "1") (pinfunction "1_1") (pintype "passive"))
      (node (ref "R9") (pin "1") (pinfunction "1_1") (pintype "passive"))
      (node (ref "S4") (pin "2") (pinfunction "P_2") (pintype "passive"))
      (node (ref "U2") (pin "11") (pinfunction "VAUX_11") (pintype "bidirectional"))
      (node (ref "U2") (pin "12") (pinfunction "VIN_12") (pintype "output"))
    )
    (net (code "55") (name "Net-(S6-S)") (class "Default")
      (node (ref "R8") (pin "1") (pinfunction "1_1") (pintype "passive"))
      (node (ref "S6") (pin "3") (pinfunction "S_3") (pintype "passive"))
    )
    (net (code "56") (name "Net-(U1-SW)") (class "Default")
      (node (ref "D1") (pin "A") (pinfunction "A_A") (pintype "passive"))
      (node (ref "L1") (pin "2") (pinfunction "2_2") (pintype "passive"))
      (node (ref "U1") (pin "1") (pinfunction "SW_1") (pintype "power_in"))
    )
    (net (code "57") (name "Net-(U2-ADJ)") (class "Default")
      (node (ref "R4") (pin "1") (pinfunction "1_1") (pintype "passive"))
      (node (ref "U2") (pin "1") (pinfunction "ADJ_1") (pintype "bidirectional"))
      (node (ref "U2") (pin "2") (pinfunction "REF_2") (pintype "input"))
      (node (ref "U2") (pin "3") (pinfunction "TADJ_3") (pintype "bidirectional"))
    )
    (net (code "58") (name "Net-(U2-GATE)") (class "Default")
      (node (ref "R7") (pin "1") (pinfunction "1_1") (pintype "passive"))
      (node (ref "U2") (pin "10") (pinfunction "GATE_10") (pintype "input"))
    )
    (net (code "59") (name "Net-(U2-GI)") (class "Default")
      (node (ref "R4") (pin "2") (pinfunction "2_2") (pintype "passive"))
      (node (ref "R6") (pin "1") (pinfunction "1_1") (pintype "passive"))
      (node (ref "U2") (pin "16") (pinfunction "GI_16") (pintype "bidirectional"))
    )
    (net (code "60") (name "Net-(U2-ISM)") (class "Default")
      (node (ref "L3") (pin "1") (pinfunction "1_1") (pintype "passive"))
      (node (ref "R5") (pin "2") (pinfunction "2_2") (pintype "passive"))
      (node (ref "R9") (pin "2") (pinfunction "2_2") (pintype "passive"))
      (node (ref "U2") (pin "13") (pinfunction "ISM_13") (pintype "bidirectional"))
    )
    (net (code "61") (name "Net-(U2-SHP)") (class "Default")
      (node (ref "C6") (pin "2") (pinfunction "2_2") (pintype "passive"))
      (node (ref "U2") (pin "4") (pinfunction "SHP_4") (pintype "bidirectional"))
    )
    (net (code "62") (name "Net-(U3-SW)") (class "Default")
      (node (ref "D10") (pin "A") (pinfunction "A_A") (pintype "passive"))
      (node (ref "L4") (pin "2") (pinfunction "2_2") (pintype "passive"))
      (node (ref "U3") (pin "1") (pinfunction "SW_1") (pintype "power_in"))
    )
    (net (code "63") (name "Net-(U4-SW)") (class "Default")
      (node (ref "D5") (pin "A") (pinfunction "A_A") (pintype "passive"))
      (node (ref "L5") (pin "2") (pinfunction "2_2") (pintype "passive"))
      (node (ref "U4") (pin "1") (pinfunction "SW_1") (pintype "power_in"))
    )
    (net (code "64") (name "Net-(U5-SW)") (class "Default")
      (node (ref "D6") (pin "A") (pinfunction "A_A") (pintype "passive"))
      (node (ref "L6") (pin "2") (pinfunction "2_2") (pintype "passive"))
      (node (ref "U5") (pin "1") (pinfunction "SW_1") (pintype "power_in"))
    )
    (net (code "65") (name "Net-(U6-ADJ)") (class "Default")
      (node (ref "R18") (pin "1") (pinfunction "1_1") (pintype "passive"))
      (node (ref "U6") (pin "1") (pinfunction "ADJ_1") (pintype "bidirectional"))
      (node (ref "U6") (pin "2") (pinfunction "REF_2") (pintype "input"))
      (node (ref "U6") (pin "3") (pinfunction "TADJ_3") (pintype "bidirectional"))
    )
    (net (code "66") (name "Net-(U6-GATE)") (class "Default")
      (node (ref "R22") (pin "1") (pinfunction "1_1") (pintype "passive"))
      (node (ref "U6") (pin "10") (pinfunction "GATE_10") (pintype "input"))
    )
    (net (code "67") (name "Net-(U6-GI)") (class "Default")
      (node (ref "R18") (pin "2") (pinfunction "2_2") (pintype "passive"))
      (node (ref "R21") (pin "1") (pinfunction "1_1") (pintype "passive"))
      (node (ref "U6") (pin "16") (pinfunction "GI_16") (pintype "bidirectional"))
    )
    (net (code "68") (name "Net-(U6-ISM)") (class "Default")
      (node (ref "L2") (pin "1") (pinfunction "1_1") (pintype "passive"))
      (node (ref "R2") (pin "2") (pinfunction "2_2") (pintype "passive"))
      (node (ref "R3") (pin "2") (pinfunction "2_2") (pintype "passive"))
      (node (ref "U6") (pin "13") (pinfunction "ISM_13") (pintype "bidirectional"))
    )
    (net (code "69") (name "Net-(U6-SHP)") (class "Default")
      (node (ref "C9") (pin "2") (pinfunction "2_2") (pintype "passive"))
      (node (ref "U6") (pin "4") (pinfunction "SHP_4") (pintype "bidirectional"))
    )
    (net (code "70") (name "Net-(U7-LED8)") (class "Default")
      (node (ref "RN3") (pin "1") (pinfunction "1_1") (pintype "passive"))
      (node (ref "U7") (pin "15") (pinfunction "LED8_15") (pintype "output"))
    )
    (net (code "71") (name "Net-(U7-LED12)") (class "Default")
      (node (ref "RN4") (pin "1") (pinfunction "1_1") (pintype "passive"))
      (node (ref "U7") (pin "19") (pinfunction "LED12_19") (pintype "output"))
    )
    (net (code "72") (name "Net-(U8-VCAP)") (class "Default")
      (node (ref "C41") (pin "+") (pinfunction "+_+") (pintype "passive"))
      (node (ref "U8") (pin "56") (pinfunction "VCAP_56") (pintype "bidirectional"))
    )
    (net (code "73") (name "Net-(U9-CB)") (class "Default")
      (node (ref "C42") (pin "1") (pinfunction "1_1") (pintype "passive"))
      (node (ref "U9") (pin "6") (pinfunction "CB_6") (pintype "bidirectional"))
    )
    (net (code "74") (name "Net-(U9-FB)") (class "Default")
      (node (ref "R52") (pin "2") (pinfunction "2_2") (pintype "passive"))
      (node (ref "R53") (pin "1") (pinfunction "1_1") (pintype "passive"))
      (node (ref "U9") (pin "4") (pinfunction "FB_4") (pintype "bidirectional"))
    )
    (net (code "75") (name "Net-(U9-SW)") (class "Default")
      (node (ref "C42") (pin "2") (pinfunction "2_2") (pintype "passive"))
      (node (ref "L7") (pin "1") (pinfunction "1_1") (pintype "passive"))
      (node (ref "U9") (pin "2") (pinfunction "SW_2") (pintype "input"))
    )
    (net (code "76") (name "Net-(U11-SW)") (class "Default")
      (node (ref "D12") (pin "A") (pinfunction "A_A") (pintype "passive"))
      (node (ref "L8") (pin "2") (pinfunction "2_2") (pintype "passive"))
      (node (ref "U11") (pin "1") (pinfunction "SW_1") (pintype "power_in"))
    )
    (net (code "77") (name "Net-(U12-SW)") (class "Default")
      (node (ref "D14") (pin "A") (pinfunction "A_A") (pintype "passive"))
      (node (ref "L9") (pin "2") (pinfunction "2_2") (pintype "passive"))
      (node (ref "U12") (pin "1") (pinfunction "SW_1") (pintype "power_in"))
    )
    (net (code "78") (name "Net-(U13-SW)") (class "Default")
      (node (ref "D15") (pin "A") (pinfunction "A_A") (pintype "passive"))
      (node (ref "L10") (pin "2") (pinfunction "2_2") (pintype "passive"))
      (node (ref "U13") (pin "1") (pinfunction "SW_1") (pintype "power_in"))
    )
    (net (code "79") (name "Net-(U14-SW)") (class "Default")
      (node (ref "D16") (pin "A") (pinfunction "A_A") (pintype "passive"))
      (node (ref "L11") (pin "2") (pinfunction "2_2") (pintype "passive"))
      (node (ref "U14") (pin "1") (pinfunction "SW_1") (pintype "power_in"))
    )
    (net (code "80") (name "OE") (class "Default")
      (node (ref "U7") (pin "23") (pinfunction "~{OE}_23") (pintype "input"))
      (node (ref "U8") (pin "46") (pinfunction "RD0_46") (pintype "bidirectional"))
    )
    (net (code "81") (name "OVP{slash}PWM_TAIL_MID") (class "Default")
      (node (ref "T3") (pin "1") (pinfunction "D_1") (pintype "passive"))
      (node (ref "U2") (pin "15") (pinfunction "PWM_15") (pintype "power_in"))
    )
    (net (code "82") (name "P1") (class "Default")
      (node (ref "C34") (pin "1") (pinfunction "1_1") (pintype "passive"))
      (node (ref "R24") (pin "2") (pinfunction "2_2") (pintype "passive"))
      (node (ref "U8") (pin "31") (pinfunction "RF4_31") (pintype "bidirectional"))
      (node (ref "X1") (pin "P$5") (pinfunction "P1_P$5") (pintype "bidirectional"))
    )
    (net (code "83") (name "P2") (class "Default")
      (node (ref "C33") (pin "1") (pinfunction "1_1") (pintype "passive"))
      (node (ref "R27") (pin "2") (pinfunction "2_2") (pintype "passive"))
      (node (ref "U8") (pin "28") (pinfunction "RB13_28") (pintype "bidirectional"))
      (node (ref "X1") (pin "P$1") (pinfunction "P2_P$1") (pintype "bidirectional"))
    )
    (net (code "84") (name "P3") (class "Default")
      (node (ref "C35") (pin "1") (pinfunction "1_1") (pintype "passive"))
      (node (ref "R25") (pin "2") (pinfunction "2_2") (pintype "passive"))
      (node (ref "U8") (pin "29") (pinfunction "RB14_29") (pintype "bidirectional"))
      (node (ref "X1") (pin "P$4") (pinfunction "P3_P$4") (pintype "bidirectional"))
    )
    (net (code "85") (name "P4") (class "Default")
      (node (ref "C36") (pin "1") (pinfunction "1_1") (pintype "passive"))
      (node (ref "R26") (pin "2") (pinfunction "2_2") (pintype "passive"))
      (node (ref "U8") (pin "30") (pinfunction "RB15_30") (pintype "bidirectional"))
      (node (ref "X1") (pin "P$2") (pinfunction "P4_P$2") (pintype "bidirectional"))
    )
    (net (code "86") (name "PGC") (class "Default")
      (node (ref "U8") (pin "14") (pinfunction "RB2_14") (pintype "bidirectional"))
      (node (ref "X2") (pin "P$3") (pinfunction "3_P$3") (pintype "bidirectional"))
    )
    (net (code "87") (name "PGD") (class "Default")
      (node (ref "U8") (pin "13") (pinfunction "RB3_13") (pintype "bidirectional"))
      (node (ref "X2") (pin "P$2") (pinfunction "2_P$2") (pintype "bidirectional"))
    )
    (net (code "88") (name "PWM") (class "Default")
      (node (ref "U6") (pin "15") (pinfunction "PWM_15") (pintype "power_in"))
    )
    (net (code "89") (name "PWM8") (class "Default")
      (node (ref "RN2") (pin "4") (pinfunction "1_4") (pintype "passive"))
    )
    (net (code "90") (name "PWM9") (class "Default")
      (node (ref "RN3") (pin "8") (pinfunction "2_8") (pintype "passive"))
    )
    (net (code "91") (name "PWM10") (class "Default")
      (node (ref "RN4") (pin "5") (pinfunction "2_5") (pintype "passive"))
    )
    (net (code "92") (name "PWM11") (class "Default")
      (node (ref "RN4") (pin "6") (pinfunction "2_6") (pintype "passive"))
    )
    (net (code "93") (name "PWM12") (class "Default")
      (node (ref "RN4") (pin "7") (pinfunction "2_7") (pintype "passive"))
    )
    (net (code "94") (name "PWM13") (class "Default")
      (node (ref "RN4") (pin "8") (pinfunction "2_8") (pintype "passive"))
    )
    (net (code "95") (name "PWM14") (class "Default")
      (node (ref "RN3") (pin "7") (pinfunction "2_7") (pintype "passive"))
    )
    (net (code "96") (name "PWM15") (class "Default")
      (node (ref "RN3") (pin "6") (pinfunction "2_6") (pintype "passive"))
    )
    (net (code "97") (name "PWM16") (class "Default")
      (node (ref "RN3") (pin "5") (pinfunction "2_5") (pintype "passive"))
    )
    (net (code "98") (name "PWM_CHMSL") (class "Default")
      (node (ref "RN2") (pin "3") (pinfunction "1_3") (pintype "passive"))
      (node (ref "U14") (pin "4") (pinfunction "CTRL_4") (pintype "power_in"))
    )
    (net (code "99") (name "PWM_LET") (class "Default")
      (node (ref "RN2") (pin "2") (pinfunction "1_2") (pintype "passive"))
      (node (ref "U13") (pin "4") (pinfunction "CTRL_4") (pintype "power_in"))
    )
    (net (code "100") (name "PWM_TAIL_LOW") (class "Default")
      (node (ref "RN2") (pin "1") (pinfunction "1_1") (pintype "passive"))
      (node (ref "U5") (pin "4") (pinfunction "CTRL_4") (pintype "power_in"))
    )
    (net (code "101") (name "PWM_TAIL_MID") (class "Default")
      (node (ref "R15") (pin "2") (pinfunction "2_2") (pintype "passive"))
      (node (ref "RN1") (pin "4") (pinfunction "1_4") (pintype "passive"))
      (node (ref "T3") (pin "3") (pinfunction "G_3") (pintype "passive"))
    )
    (net (code "102") (name "PWM_TAIL_UPP") (class "Default")
      (node (ref "RN1") (pin "3") (pinfunction "1_3") (pintype "passive"))
      (node (ref "U4") (pin "4") (pinfunction "CTRL_4") (pintype "power_in"))
    )
    (net (code "103") (name "PWM_TI") (class "Default")
      (node (ref "S6") (pin "1") (pinfunction "O_1") (pintype "passive"))
      (node (ref "U8") (pin "49") (pinfunction "RD1_49") (pintype "bidirectional"))
    )
    (net (code "104") (name "PWM_T{slash}B_LOW") (class "Default")
      (node (ref "RN1") (pin "2") (pinfunction "1_2") (pintype "passive"))
      (node (ref "S7") (pin "21") (pinfunction "6_21") (pintype "bidirectional"))
    )
    (net (code "105") (name "PWM_T{slash}B_UPP") (class "Default")
      (node (ref "RN1") (pin "1") (pinfunction "1_1") (pintype "passive"))
      (node (ref "S7") (pin "11") (pinfunction "3_11") (pintype "bidirectional"))
    )
    (net (code "106") (name "RE7") (class "Default")
      (node (ref "U8") (pin "3") (pinfunction "RE7_3") (pintype "power_in"))
    )
    (net (code "107") (name "RESET") (class "Default")
      (node (ref "C28") (pin "1") (pinfunction "1_1") (pintype "passive"))
      (node (ref "S2") (pin "3") (pinfunction "2_3") (pintype "passive"))
      (node (ref "U8") (pin "22") (pinfunction "RB9_22") (pintype "bidirectional"))
    )
    (net (code "108") (name "REV") (class "Default")
      (node (ref "JP2") (pin "5") (pinfunction "5_5") (pintype "passive"))
      (node (ref "Q10") (pin "1") (pinfunction "D_1") (pintype "passive"))
      (node (ref "Q10") (pin "2") (pinfunction "D_2") (pintype "passive"))
      (node (ref "Q10") (pin "5") (pinfunction "D_5") (pintype "passive"))
      (node (ref "Q10") (pin "6") (pinfunction "D_6") (pintype "passive"))
    )
    (net (code "109") (name "REV_A") (class "Default")
      (node (ref "C53") (pin "1") (pinfunction "1_1") (pintype "passive"))
      (node (ref "D14") (pin "C") (pinfunction "C_C") (pintype "passive"))
      (node (ref "JP5") (pin "6") (pinfunction "6_6") (pintype "passive"))
    )
    (net (code "110") (name "REV_K") (class "Default")
      (node (ref "JP5") (pin "5") (pinfunction "5_5") (pintype "passive"))
      (node (ref "R38") (pin "1") (pinfunction "1_1") (pintype "passive"))
      (node (ref "U12") (pin "3") (pinfunction "FB_3") (pintype "input"))
    )
    (net (code "111") (name "ROT_+") (class "Default")
      (node (ref "C37") (pin "1") (pinfunction "1_1") (pintype "passive"))
      (node (ref "R28") (pin "2") (pinfunction "2_2") (pintype "passive"))
      (node (ref "U8") (pin "27") (pinfunction "RB12_27") (pintype "bidirectional"))
      (node (ref "X3") (pin "P$1") (pinfunction "P1_P$1") (pintype "bidirectional"))
    )
    (net (code "112") (name "ROT_-") (class "Default")
      (node (ref "C38") (pin "1") (pinfunction "1_1") (pintype "passive"))
      (node (ref "R29") (pin "2") (pinfunction "2_2") (pintype "passive"))
      (node (ref "U8") (pin "24") (pinfunction "RB11_24") (pintype "bidirectional"))
      (node (ref "X3") (pin "P$3") (pinfunction "P2_P$3") (pintype "bidirectional"))
    )
    (net (code "113") (name "SCL") (class "Default")
      (node (ref "JP1") (pin "3") (pinfunction "3_3") (pintype "passive"))
      (node (ref "R34") (pin "2") (pinfunction "2_2") (pintype "passive"))
      (node (ref "U10") (pin "6") (pinfunction "SCL_6") (pintype "bidirectional"))
      (node (ref "U7") (pin "26") (pinfunction "SCL_26") (pintype "input"))
      (node (ref "U8") (pin "37") (pinfunction "RG2_37") (pintype "power_in"))
    )
    (net (code "114") (name "SDA") (class "Default")
      (node (ref "JP1") (pin "4") (pinfunction "4_4") (pintype "passive"))
      (node (ref "R33") (pin "2") (pinfunction "2_2") (pintype "passive"))
      (node (ref "U10") (pin "5") (pinfunction "SDA_5") (pintype "bidirectional"))
      (node (ref "U7") (pin "27") (pinfunction "SDA_27") (pintype "bidirectional"))
      (node (ref "U8") (pin "36") (pinfunction "RG3_36") (pintype "input"))
    )
    (net (code "115") (name "TAIL") (class "Default")
      (node (ref "JP2") (pin "3") (pinfunction "3_3") (pintype "passive"))
      (node (ref "Q7") (pin "1") (pinfunction "D_1") (pintype "passive"))
      (node (ref "Q7") (pin "2") (pinfunction "D_2") (pintype "passive"))
      (node (ref "Q7") (pin "5") (pinfunction "D_5") (pintype "passive"))
      (node (ref "Q7") (pin "6") (pinfunction "D_6") (pintype "passive"))
    )
    (net (code "116") (name "TAIL_LOW_A") (class "Default")
      (node (ref "C24") (pin "1") (pinfunction "1_1") (pintype "passive"))
      (node (ref "D6") (pin "C") (pinfunction "C_C") (pintype "passive"))
      (node (ref "JP3") (pin "10") (pinfunction "10_10") (pintype "passive"))
    )
    (net (code "117") (name "TAIL_LOW_K") (class "Default")
      (node (ref "JP3") (pin "9") (pinfunction "9_9") (pintype "passive"))
      (node (ref "R11") (pin "1") (pinfunction "1_1") (pintype "passive"))
      (node (ref "U5") (pin "3") (pinfunction "FB_3") (pintype "input"))
    )
    (net (code "118") (name "TAIL_MID_A") (class "Default")
      (node (ref "C16") (pin "2") (pinfunction "2_2") (pintype "passive"))
      (node (ref "C17") (pin "2") (pinfunction "2_2") (pintype "passive"))
      (node (ref "C18") (pin "2") (pinfunction "2_2") (pintype "passive"))
      (node (ref "C8") (pin "2") (pinfunction "2_2") (pintype "passive"))
      (node (ref "D3") (pin "C") (pinfunction "C_C") (pintype "passive"))
      (node (ref "JP3") (pin "11") (pinfunction "11_11") (pintype "passive"))
    )
    (net (code "119") (name "TAIL_UPP_A") (class "Default")
      (node (ref "C22") (pin "1") (pinfunction "1_1") (pintype "passive"))
      (node (ref "D5") (pin "C") (pinfunction "C_C") (pintype "passive"))
      (node (ref "JP3") (pin "8") (pinfunction "8_8") (pintype "passive"))
    )
    (net (code "120") (name "TAIL_UPP_K") (class "Default")
      (node (ref "JP3") (pin "7") (pinfunction "7_7") (pintype "passive"))
      (node (ref "R10") (pin "1") (pinfunction "1_1") (pintype "passive"))
      (node (ref "U4") (pin "3") (pinfunction "FB_3") (pintype "input"))
    )
    (net (code "121") (name "TI") (class "Default")
      (node (ref "JP2") (pin "1") (pinfunction "1_1") (pintype "passive"))
      (node (ref "Q5") (pin "1") (pinfunction "D_1") (pintype "passive"))
      (node (ref "Q5") (pin "2") (pinfunction "D_2") (pintype "passive"))
      (node (ref "Q5") (pin "5") (pinfunction "D_5") (pintype "passive"))
      (node (ref "Q5") (pin "6") (pinfunction "D_6") (pintype "passive"))
    )
    (net (code "122") (name "TI_A") (class "Default")
      (node (ref "C11") (pin "2") (pinfunction "2_2") (pintype "passive"))
      (node (ref "C3") (pin "2") (pinfunction "2_2") (pintype "passive"))
      (node (ref "C4") (pin "2") (pinfunction "2_2") (pintype "passive"))
      (node (ref "C5") (pin "2") (pinfunction "2_2") (pintype "passive"))
      (node (ref "D11") (pin "C") (pinfunction "C_C") (pintype "passive"))
      (node (ref "JP3") (pin "2") (pinfunction "2_2") (pintype "passive"))
    )
    (net (code "123") (name "T{slash}B") (class "Default")
      (node (ref "JP2") (pin "2") (pinfunction "2_2") (pintype "passive"))
      (node (ref "Q6") (pin "1") (pinfunction "D_1") (pintype "passive"))
      (node (ref "Q6") (pin "2") (pinfunction "D_2") (pintype "passive"))
      (node (ref "Q6") (pin "5") (pinfunction "D_5") (pintype "passive"))
      (node (ref "Q6") (pin "6") (pinfunction "D_6") (pintype "passive"))
    )
    (net (code "124") (name "T{slash}B_LOW_OUT_A") (class "Default")
      (node (ref "C2") (pin "1") (pinfunction "1_1") (pintype "passive"))
      (node (ref "D1") (pin "C") (pinfunction "C_C") (pintype "passive"))
      (node (ref "JP3") (pin "6") (pinfunction "6_6") (pintype "passive"))
    )
    (net (code "125") (name "T{slash}B_LOW_OUT_K") (class "Default")
      (node (ref "JP3") (pin "5") (pinfunction "5_5") (pintype "passive"))
      (node (ref "R1") (pin "1") (pinfunction "1_1") (pintype "passive"))
      (node (ref "U1") (pin "3") (pinfunction "FB_3") (pintype "input"))
    )
    (net (code "126") (name "T{slash}B_UPP_OUT_A") (class "Default")
      (node (ref "C15") (pin "1") (pinfunction "1_1") (pintype "passive"))
      (node (ref "D10") (pin "C") (pinfunction "C_C") (pintype "passive"))
      (node (ref "JP3") (pin "3") (pinfunction "3_3") (pintype "passive"))
    )
    (net (code "127") (name "T{slash}B_UPP_OUT_K") (class "Default")
      (node (ref "JP3") (pin "1") (pinfunction "1_1") (pintype "passive"))
      (node (ref "R19") (pin "1") (pinfunction "1_1") (pintype "passive"))
      (node (ref "U3") (pin "3") (pinfunction "FB_3") (pintype "input"))
    )
    (net (code "128") (name "VCC") (class "Default")
      (node (ref "JP2") (pin "8") (pinfunction "8_8") (pintype "passive"))
      (node (ref "Q8") (pin "1") (pinfunction "D_1") (pintype "passive"))
      (node (ref "Q8") (pin "2") (pinfunction "D_2") (pintype "passive"))
      (node (ref "Q8") (pin "5") (pinfunction "D_5") (pintype "passive"))
      (node (ref "Q8") (pin "6") (pinfunction "D_6") (pintype "passive"))
    )
    (net (code "129") (name "V_CHMSL") (class "Default")
      (node (ref "C56") (pin "1") (pinfunction "1_1") (pintype "passive"))
      (node (ref "D20") (pin "C") (pinfunction "C_C") (pintype "passive"))
      (node (ref "L11") (pin "1") (pinfunction "1_1") (pintype "passive"))
      (node (ref "Q12") (pin "4") (pinfunction "S_4") (pintype "passive"))
      (node (ref "U14") (pin "6") (pinfunction "VIN_6") (pintype "output"))
    )
    (net (code "130") (name "V_FOG") (class "Default")
      (node (ref "C50") (pin "1") (pinfunction "1_1") (pintype "passive"))
      (node (ref "D17") (pin "C") (pinfunction "C_C") (pintype "passive"))
      (node (ref "L8") (pin "1") (pinfunction "1_1") (pintype "passive"))
      (node (ref "Q9") (pin "4") (pinfunction "S_4") (pintype "passive"))
      (node (ref "U11") (pin "6") (pinfunction "VIN_6") (pintype "output"))
    )
    (net (code "131") (name "V_LET") (class "Default")
      (node (ref "C54") (pin "1") (pinfunction "1_1") (pintype "passive"))
      (node (ref "D19") (pin "C") (pinfunction "C_C") (pintype "passive"))
      (node (ref "L10") (pin "1") (pinfunction "1_1") (pintype "passive"))
      (node (ref "Q11") (pin "4") (pinfunction "S_4") (pintype "passive"))
      (node (ref "U13") (pin "6") (pinfunction "VIN_6") (pintype "output"))
    )
    (net (code "132") (name "V_REV") (class "Default")
      (node (ref "C52") (pin "1") (pinfunction "1_1") (pintype "passive"))
      (node (ref "D18") (pin "C") (pinfunction "C_C") (pintype "passive"))
      (node (ref "L9") (pin "1") (pinfunction "1_1") (pintype "passive"))
      (node (ref "Q10") (pin "4") (pinfunction "S_4") (pintype "passive"))
      (node (ref "U12") (pin "6") (pinfunction "VIN_6") (pintype "output"))
    )
    (net (code "133") (name "V_TAIL") (class "Default")
      (node (ref "C21") (pin "1") (pinfunction "1_1") (pintype "passive"))
      (node (ref "C23") (pin "1") (pinfunction "1_1") (pintype "passive"))
      (node (ref "D8") (pin "C") (pinfunction "C_C") (pintype "passive"))
      (node (ref "L5") (pin "1") (pinfunction "1_1") (pintype "passive"))
      (node (ref "L6") (pin "1") (pinfunction "1_1") (pintype "passive"))
      (node (ref "Q7") (pin "4") (pinfunction "S_4") (pintype "passive"))
      (node (ref "S4") (pin "3") (pinfunction "S_3") (pintype "passive"))
      (node (ref "U4") (pin "6") (pinfunction "VIN_6") (pintype "output"))
      (node (ref "U5") (pin "6") (pinfunction "VIN_6") (pintype "output"))
    )
    (net (code "134") (name "V_TI") (class "Default")
      (node (ref "D13") (pin "C") (pinfunction "C_C") (pintype "passive"))
      (node (ref "Q4") (pin "4") (pinfunction "S_4") (pintype "passive"))
      (node (ref "Q5") (pin "4") (pinfunction "S_4") (pintype "passive"))
      (node (ref "R14") (pin "2") (pinfunction "2_2") (pintype "passive"))
      (node (ref "R8") (pin "2") (pinfunction "2_2") (pintype "passive"))
    )
    (net (code "135") (name "V_TI_BOOST") (class "Default")
      (node (ref "C10") (pin "2") (pinfunction "2_2") (pintype "passive"))
      (node (ref "C19") (pin "2") (pinfunction "2_2") (pintype "passive"))
      (node (ref "C20") (pin "2") (pinfunction "2_2") (pintype "passive"))
      (node (ref "C25") (pin "1") (pinfunction "1_1") (pintype "passive"))
      (node (ref "Q4") (pin "1") (pinfunction "D_1") (pintype "passive"))
      (node (ref "Q4") (pin "2") (pinfunction "D_2") (pintype "passive"))
      (node (ref "Q4") (pin "5") (pinfunction "D_5") (pintype "passive"))
      (node (ref "Q4") (pin "6") (pinfunction "D_6") (pintype "passive"))
      (node (ref "R2") (pin "1") (pinfunction "1_1") (pintype "passive"))
      (node (ref "R3") (pin "1") (pinfunction "1_1") (pintype "passive"))
      (node (ref "U6") (pin "11") (pinfunction "VAUX_11") (pintype "bidirectional"))
      (node (ref "U6") (pin "12") (pinfunction "VIN_12") (pintype "output"))
    )
    (net (code "136") (name "V_T{slash}B") (class "Default")
      (node (ref "C1") (pin "1") (pinfunction "1_1") (pintype "passive"))
      (node (ref "C12") (pin "1") (pinfunction "1_1") (pintype "passive"))
      (node (ref "D7") (pin "C") (pinfunction "C_C") (pintype "passive"))
      (node (ref "L1") (pin "1") (pinfunction "1_1") (pintype "passive"))
      (node (ref "L4") (pin "1") (pinfunction "1_1") (pintype "passive"))
      (node (ref "Q6") (pin "4") (pinfunction "S_4") (pintype "passive"))
      (node (ref "S7") (pin "10") (pinfunction "1_10") (pintype "bidirectional"))
      (node (ref "S7") (pin "20") (pinfunction "4_20") (pintype "bidirectional"))
      (node (ref "U1") (pin "6") (pinfunction "VIN_6") (pintype "output"))
      (node (ref "U3") (pin "6") (pinfunction "VIN_6") (pintype "output"))
    )
    (net (code "137") (name "unconnected-(S4-O-Pad1)") (class "Default")
      (node (ref "S4") (pin "1") (pinfunction "O_1") (pintype "passive"))
    )
    (net (code "138") (name "unconnected-(U1-OV-Pad5)") (class "Default")
      (node (ref "U1") (pin "5") (pinfunction "OV_5") (pintype "input"))
    )
    (net (code "139") (name "unconnected-(U2-STATUS-Pad5)") (class "Default")
      (node (ref "U2") (pin "5") (pinfunction "STATUS_5") (pintype "bidirectional"))
    )
    (net (code "140") (name "unconnected-(U3-OV-Pad5)") (class "Default")
      (node (ref "U3") (pin "5") (pinfunction "OV_5") (pintype "input"))
    )
    (net (code "141") (name "unconnected-(U4-OV-Pad5)") (class "Default")
      (node (ref "U4") (pin "5") (pinfunction "OV_5") (pintype "input"))
    )
    (net (code "142") (name "unconnected-(U5-OV-Pad5)") (class "Default")
      (node (ref "U5") (pin "5") (pinfunction "OV_5") (pintype "input"))
    )
    (net (code "143") (name "unconnected-(U6-FLAG-Pad14)") (class "Default")
      (node (ref "U6") (pin "14") (pinfunction "FLAG_14") (pintype "power_in"))
    )
    (net (code "144") (name "unconnected-(U6-STATUS-Pad5)") (class "Default")
      (node (ref "U6") (pin "5") (pinfunction "STATUS_5") (pintype "bidirectional"))
    )
    (net (code "145") (name "unconnected-(U7-EXTCLK-Pad25)") (class "Default")
      (node (ref "U7") (pin "25") (pinfunction "EXTCLK_25") (pintype "input"))
    )
    (net (code "146") (name "unconnected-(U8-RB0-Pad16)") (class "Default")
      (node (ref "U8") (pin "16") (pinfunction "RB0_16") (pintype "bidirectional"))
    )
    (net (code "147") (name "unconnected-(U8-RB1-Pad15)") (class "Default")
      (node (ref "U8") (pin "15") (pinfunction "RB1_15") (pintype "bidirectional"))
    )
    (net (code "148") (name "unconnected-(U8-RB4-Pad12)") (class "Default")
      (node (ref "U8") (pin "12") (pinfunction "RB4_12") (pintype "bidirectional"))
    )
    (net (code "149") (name "unconnected-(U8-RB5-Pad11)") (class "Default")
      (node (ref "U8") (pin "11") (pinfunction "RB5_11") (pintype "bidirectional"))
    )
    (net (code "150") (name "unconnected-(U8-RB8-Pad21)") (class "Default")
      (node (ref "U8") (pin "21") (pinfunction "RB8_21") (pintype "bidirectional"))
    )
    (net (code "151") (name "unconnected-(U8-RB10-Pad23)") (class "Default")
      (node (ref "U8") (pin "23") (pinfunction "RB10_23") (pintype "bidirectional"))
    )
    (net (code "152") (name "unconnected-(U8-RC14-Pad48)") (class "Default")
      (node (ref "U8") (pin "48") (pinfunction "RC14_48") (pintype "bidirectional"))
    )
    (net (code "153") (name "unconnected-(U8-RC15-Pad40)") (class "Default")
      (node (ref "U8") (pin "40") (pinfunction "RC15_40") (pintype "bidirectional"))
    )
    (net (code "154") (name "unconnected-(U8-RD2-Pad50)") (class "Default")
      (node (ref "U8") (pin "50") (pinfunction "RD2_50") (pintype "bidirectional"))
    )
    (net (code "155") (name "unconnected-(U8-RD3-Pad51)") (class "Default")
      (node (ref "U8") (pin "51") (pinfunction "RD3_51") (pintype "bidirectional"))
    )
    (net (code "156") (name "unconnected-(U8-RD4-Pad52)") (class "Default")
      (node (ref "U8") (pin "52") (pinfunction "RD4_52") (pintype "bidirectional"))
    )
    (net (code "157") (name "unconnected-(U8-RD5-Pad53)") (class "Default")
      (node (ref "U8") (pin "53") (pinfunction "RD5_53") (pintype "bidirectional"))
    )
    (net (code "158") (name "unconnected-(U8-RD6-Pad54)") (class "Default")
      (node (ref "U8") (pin "54") (pinfunction "RD6_54") (pintype "bidirectional"))
    )
    (net (code "159") (name "unconnected-(U8-RD7-Pad55)") (class "Default")
      (node (ref "U8") (pin "55") (pinfunction "RD7_55") (pintype "bidirectional"))
    )
    (net (code "160") (name "unconnected-(U8-RD8-Pad42)") (class "Default")
      (node (ref "U8") (pin "42") (pinfunction "RD8_42") (pintype "bidirectional"))
    )
    (net (code "161") (name "unconnected-(U8-RD9-Pad43)") (class "Default")
      (node (ref "U8") (pin "43") (pinfunction "RD9_43") (pintype "bidirectional"))
    )
    (net (code "162") (name "unconnected-(U8-RD10-Pad44)") (class "Default")
      (node (ref "U8") (pin "44") (pinfunction "RD10_44") (pintype "bidirectional"))
    )
    (net (code "163") (name "unconnected-(U8-RD11-Pad45)") (class "Default")
      (node (ref "U8") (pin "45") (pinfunction "RD11_45") (pintype "bidirectional"))
    )
    (net (code "164") (name "unconnected-(U8-RE0-Pad60)") (class "Default")
      (node (ref "U8") (pin "60") (pinfunction "RE0_60") (pintype "bidirectional"))
    )
    (net (code "165") (name "unconnected-(U8-RE1-Pad61)") (class "Default")
      (node (ref "U8") (pin "61") (pinfunction "RE1_61") (pintype "bidirectional"))
    )
    (net (code "166") (name "unconnected-(U8-RE2-Pad62)") (class "Default")
      (node (ref "U8") (pin "62") (pinfunction "RE2_62") (pintype "bidirectional"))
    )
    (net (code "167") (name "unconnected-(U8-RE3-Pad63)") (class "Default")
      (node (ref "U8") (pin "63") (pinfunction "RE3_63") (pintype "bidirectional"))
    )
    (net (code "168") (name "unconnected-(U8-RE4-Pad64)") (class "Default")
      (node (ref "U8") (pin "64") (pinfunction "RE4_64") (pintype "bidirectional"))
    )
    (net (code "169") (name "unconnected-(U8-RE5-Pad1)") (class "Default")
      (node (ref "U8") (pin "1") (pinfunction "RE5_1") (pintype "bidirectional"))
    )
    (net (code "170") (name "unconnected-(U8-RE6-Pad2)") (class "Default")
      (node (ref "U8") (pin "2") (pinfunction "RE6_2") (pintype "output"))
    )
    (net (code "171") (name "unconnected-(U8-RF0-Pad58)") (class "Default")
      (node (ref "U8") (pin "58") (pinfunction "RF0_58") (pintype "bidirectional"))
    )
    (net (code "172") (name "unconnected-(U8-RF1-Pad59)") (class "Default")
      (node (ref "U8") (pin "59") (pinfunction "RF1_59") (pintype "bidirectional"))
    )
    (net (code "173") (name "unconnected-(U8-RF2-Pad34)") (class "Default")
      (node (ref "U8") (pin "34") (pinfunction "RF2_34") (pintype "bidirectional"))
    )
    (net (code "174") (name "unconnected-(U8-RF3-Pad33)") (class "Default")
      (node (ref "U8") (pin "33") (pinfunction "RF3_33") (pintype "bidirectional"))
    )
    (net (code "175") (name "unconnected-(U8-RF5-Pad32)") (class "Default")
      (node (ref "U8") (pin "32") (pinfunction "RF5_32") (pintype "bidirectional"))
    )
    (net (code "176") (name "unconnected-(U8-RF6-Pad35)") (class "Default")
      (node (ref "U8") (pin "35") (pinfunction "RF6_35") (pintype "bidirectional"))
    )
    (net (code "177") (name "unconnected-(U8-RG6-Pad4)") (class "Default")
      (node (ref "U8") (pin "4") (pinfunction "RG6_4") (pintype "bidirectional"))
    )
    (net (code "178") (name "unconnected-(U8-RG7-Pad5)") (class "Default")
      (node (ref "U8") (pin "5") (pinfunction "RG7_5") (pintype "input"))
    )
    (net (code "179") (name "unconnected-(U8-RG8-Pad6)") (class "Default")
      (node (ref "U8") (pin "6") (pinfunction "RG8_6") (pintype "bidirectional"))
    )
    (net (code "180") (name "unconnected-(U8-RG9-Pad8)") (class "Default")
      (node (ref "U8") (pin "8") (pinfunction "RG9_8") (pintype "bidirectional"))
    )
    (net (code "181") (name "unconnected-(U11-CTRL-Pad4)") (class "Default")
      (node (ref "U11") (pin "4") (pinfunction "CTRL_4") (pintype "power_in"))
    )
    (net (code "182") (name "unconnected-(U11-OV-Pad5)") (class "Default")
      (node (ref "U11") (pin "5") (pinfunction "OV_5") (pintype "input"))
    )
    (net (code "183") (name "unconnected-(U12-CTRL-Pad4)") (class "Default")
      (node (ref "U12") (pin "4") (pinfunction "CTRL_4") (pintype "power_in"))
    )
    (net (code "184") (name "unconnected-(U12-OV-Pad5)") (class "Default")
      (node (ref "U12") (pin "5") (pinfunction "OV_5") (pintype "input"))
    )
    (net (code "185") (name "unconnected-(U13-OV-Pad5)") (class "Default")
      (node (ref "U13") (pin "5") (pinfunction "OV_5") (pintype "input"))
    )
    (net (code "186") (name "unconnected-(U14-OV-Pad5)") (class "Default")
      (node (ref "U14") (pin "5") (pinfunction "OV_5") (pintype "input"))
    )
    (net (code "187") (name "unconnected-(X2-NC1-PadA)") (class "Default")
      (node (ref "X2") (pin "A") (pinfunction "NC1_A") (pintype "bidirectional"))
    )
    (net (code "188") (name "unconnected-(X2-NC2-PadB)") (class "Default")
      (node (ref "X2") (pin "B") (pinfunction "NC2_B") (pintype "bidirectional"))
    )
    (net (code "189") (name "~{MCLR}") (class "Default")
      (node (ref "R16") (pin "2") (pinfunction "2_2") (pintype "passive"))
      (node (ref "U8") (pin "7") (pinfunction "MCLR_7") (pintype "bidirectional"))
      (node (ref "X2") (pin "P$4") (pinfunction "4_P$4") (pintype "bidirectional"))
    )
    (net (code "190") (name "~{WC}") (class "Default")
      (node (ref "U10") (pin "7") (pinfunction "~{WC}_7") (pintype "bidirectional"))
      (node (ref "U8") (pin "47") (pinfunction "RC13_47") (pintype "bidirectional"))
    )
  )
)
